# 20240717-7439.net
KiCad netlist of a schematic drawn in EAGLE
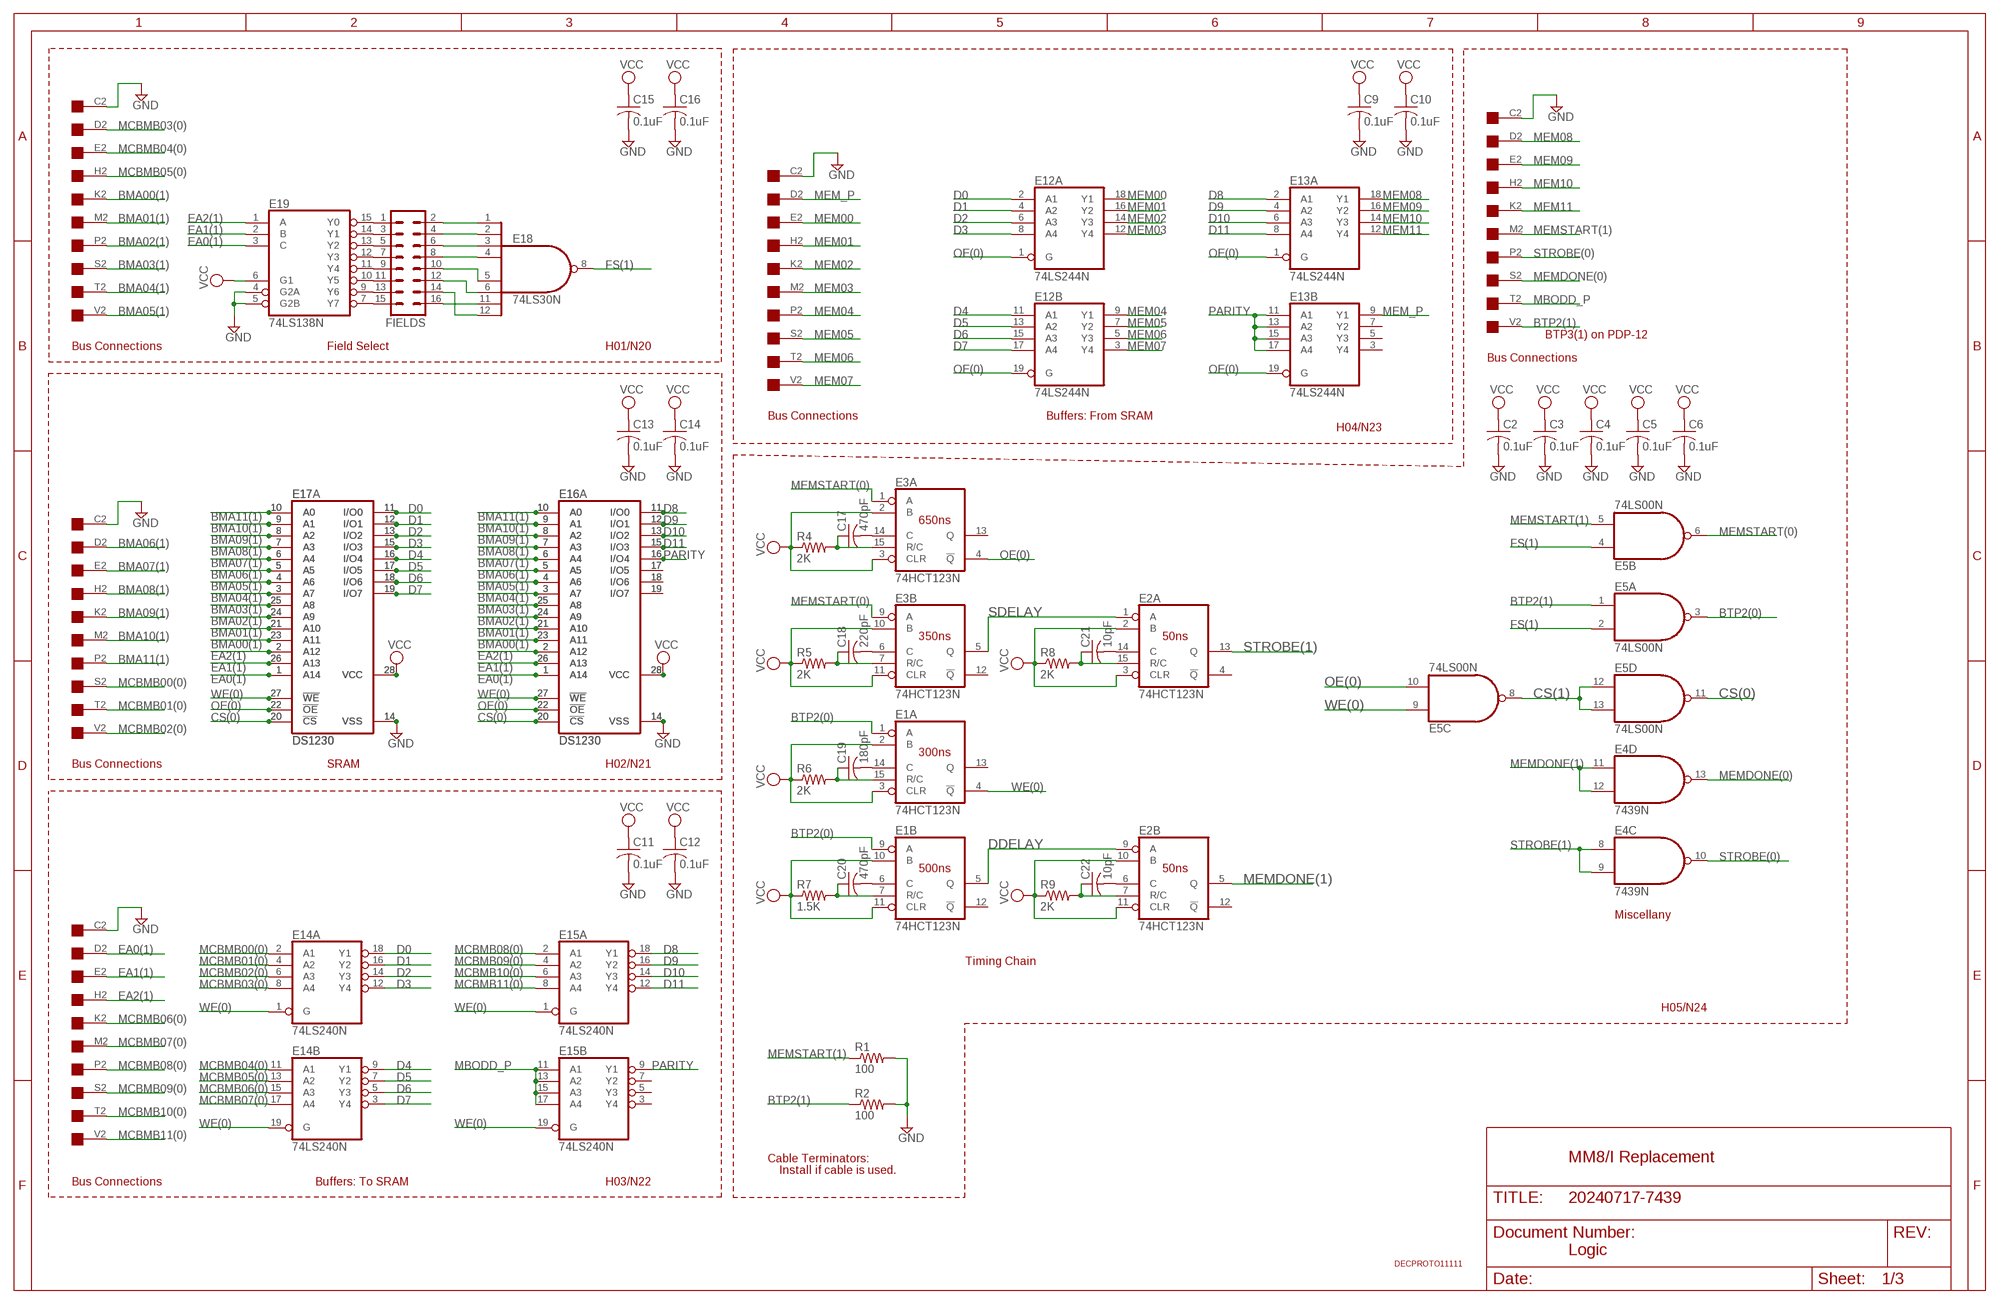
[diagram p0: schematic, sheet 1]
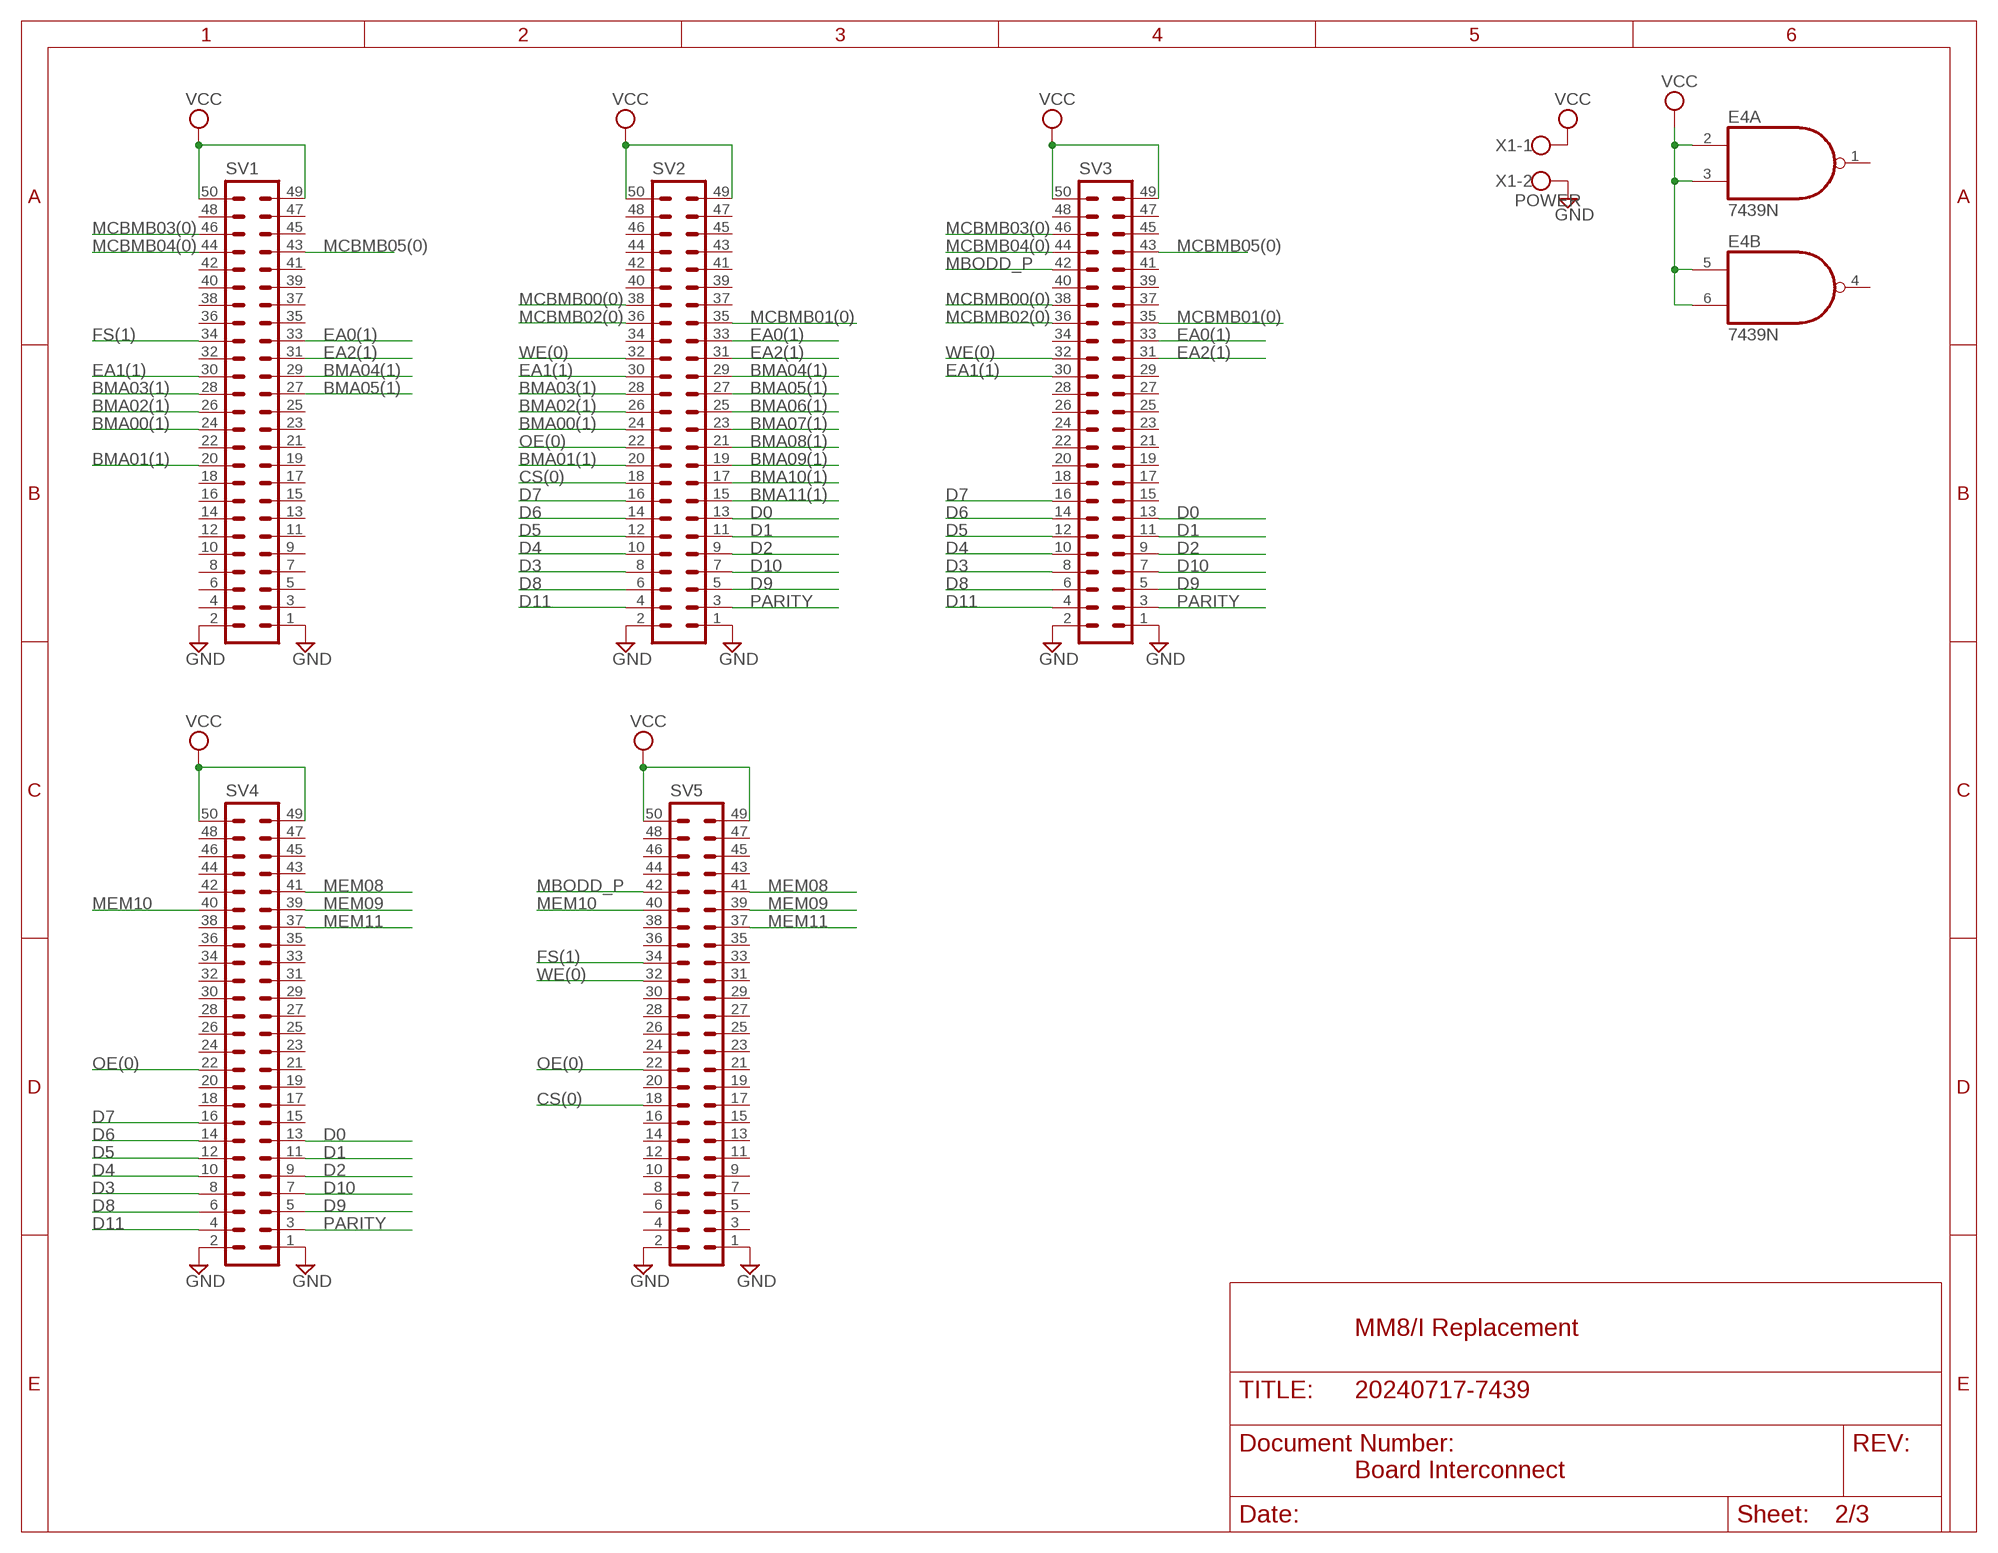
[diagram p1: schematic, sheet 2]
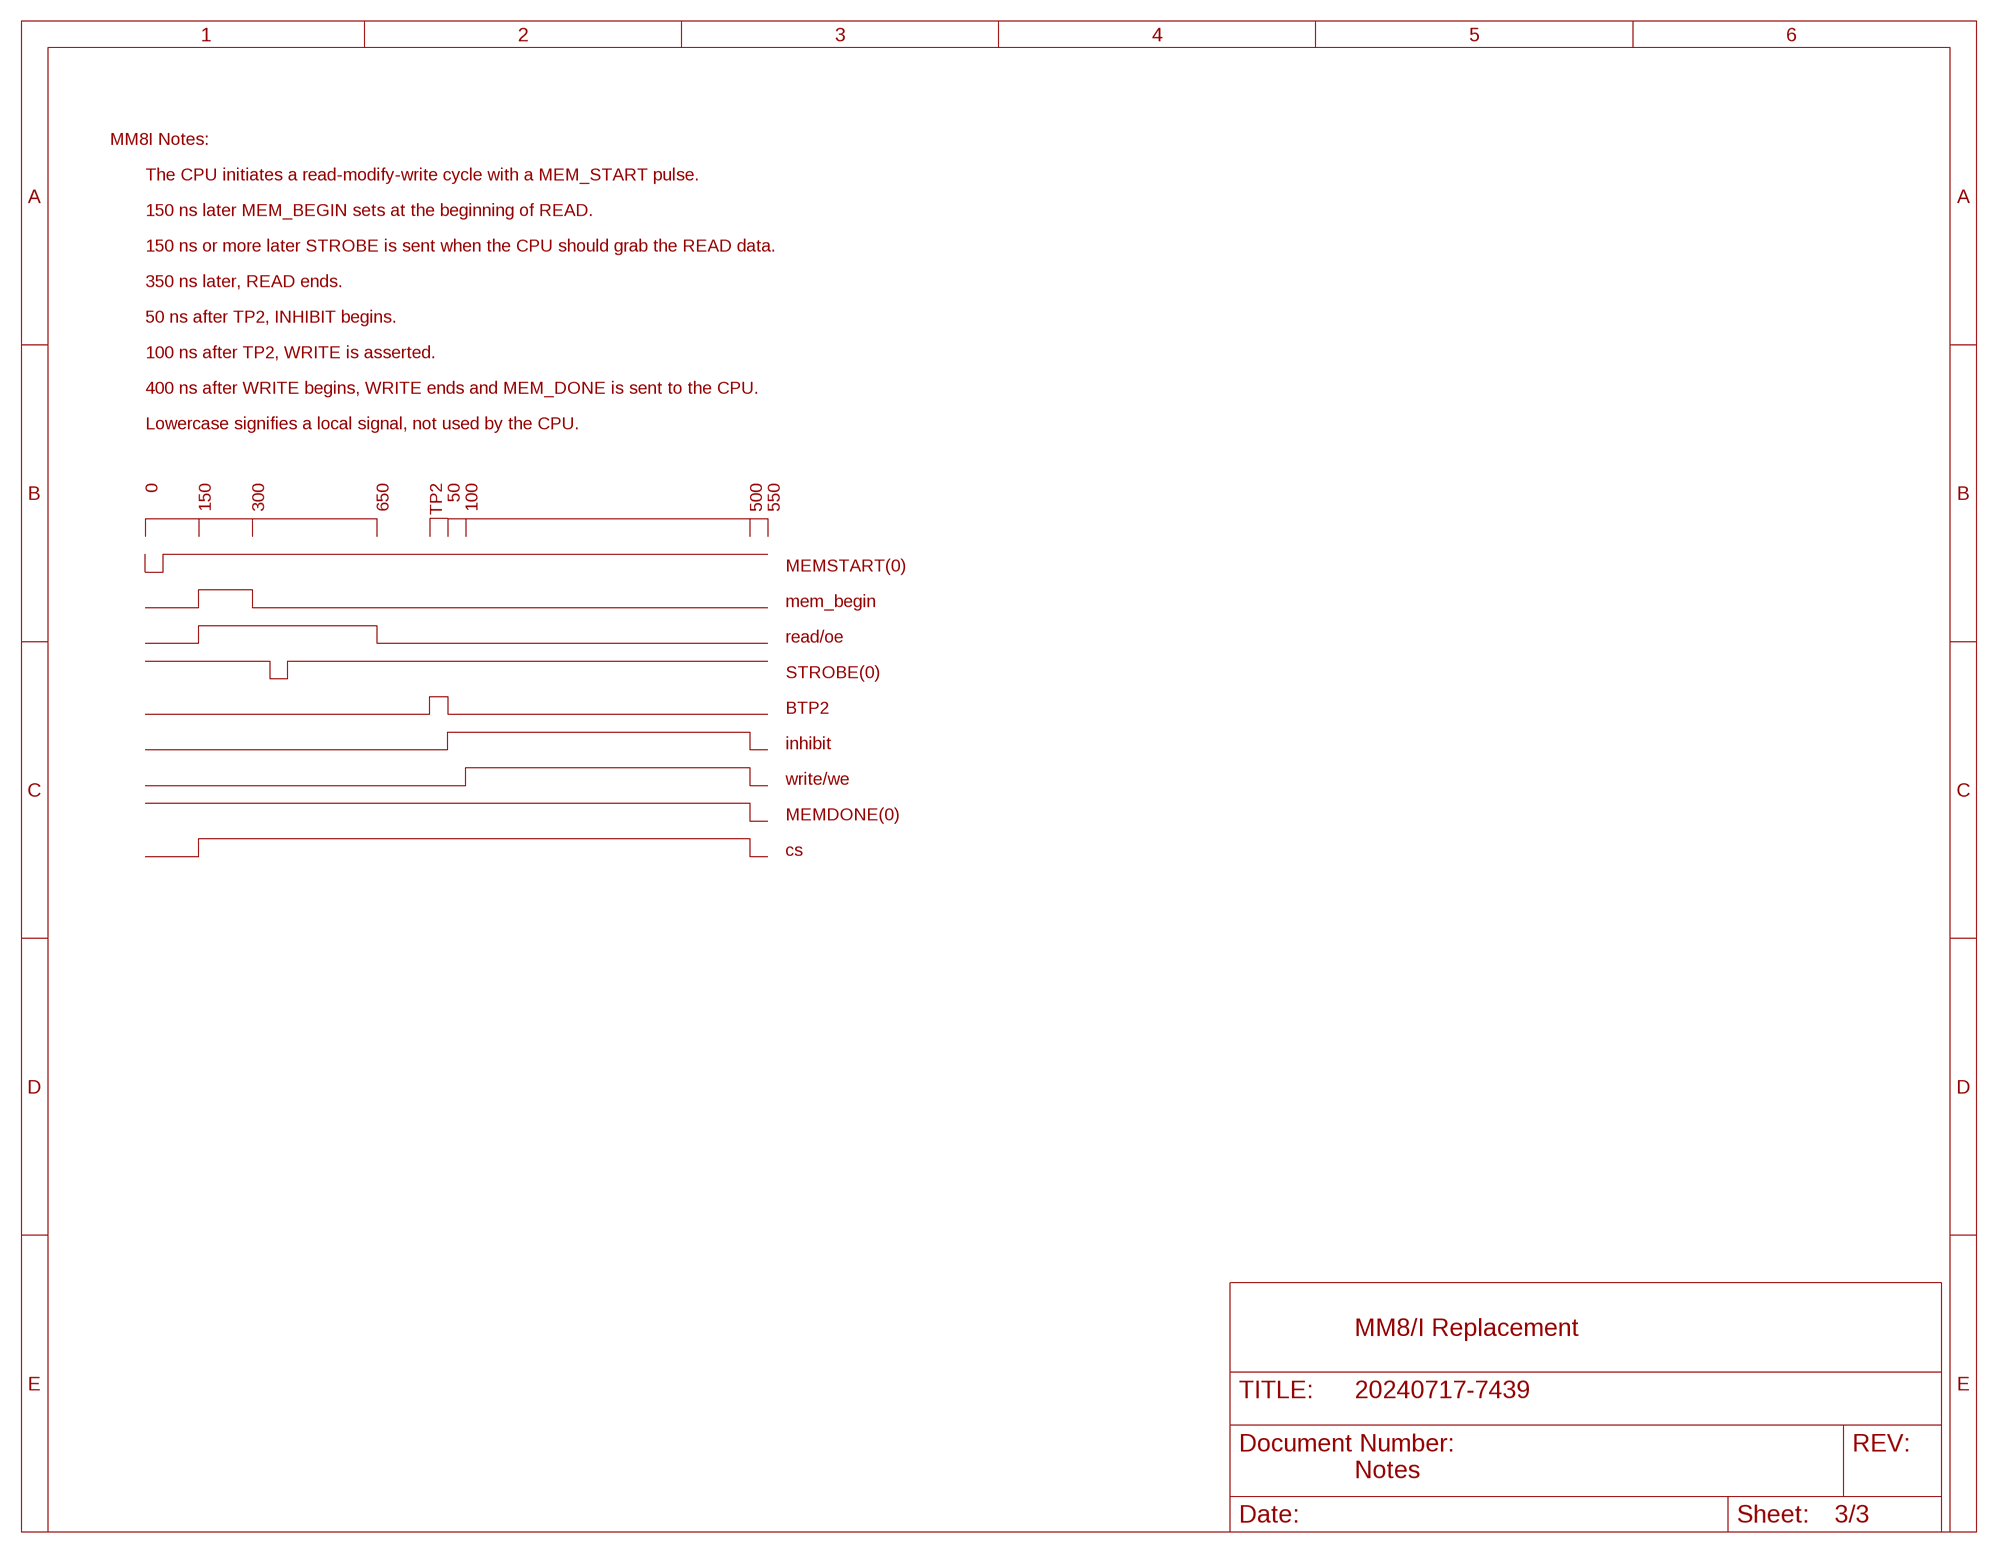
[diagram p2: schematic, sheet 3]

(export (version "E")
  (design (tool "Eeschema 10.0.6"))
  (components
    (comp (ref "C2")
      (value "0.1uF")
      (footprint "eagle-import:C050-025X075")
      (libsource (lib "eagle-import") (part "C-US050-025X075"))
    )
    (comp (ref "C3")
      (value "0.1uF")
      (footprint "eagle-import:C050-025X075")
      (libsource (lib "eagle-import") (part "C-US050-025X075"))
    )
    (comp (ref "C4")
      (value "0.1uF")
      (footprint "eagle-import:C050-025X075")
      (libsource (lib "eagle-import") (part "C-US050-025X075"))
    )
    (comp (ref "C5")
      (value "0.1uF")
      (footprint "eagle-import:C050-025X075")
      (libsource (lib "eagle-import") (part "C-US050-025X075"))
    )
    (comp (ref "C6")
      (value "0.1uF")
      (footprint "eagle-import:C050-025X075")
      (libsource (lib "eagle-import") (part "C-US050-025X075"))
    )
    (comp (ref "C9")
      (value "0.1uF")
      (footprint "eagle-import:C050-025X075")
      (libsource (lib "eagle-import") (part "C-US050-025X075"))
    )
    (comp (ref "C10")
      (value "0.1uF")
      (footprint "eagle-import:C050-025X075")
      (libsource (lib "eagle-import") (part "C-US050-025X075"))
    )
    (comp (ref "C11")
      (value "0.1uF")
      (footprint "eagle-import:C050-025X075")
      (libsource (lib "eagle-import") (part "C-US050-025X075"))
    )
    (comp (ref "C12")
      (value "0.1uF")
      (footprint "eagle-import:C050-025X075")
      (libsource (lib "eagle-import") (part "C-US050-025X075"))
    )
    (comp (ref "C13")
      (value "0.1uF")
      (footprint "eagle-import:C050-025X075")
      (libsource (lib "eagle-import") (part "C-US050-025X075"))
    )
    (comp (ref "C14")
      (value "0.1uF")
      (footprint "eagle-import:C050-025X075")
      (libsource (lib "eagle-import") (part "C-US050-025X075"))
    )
    (comp (ref "C15")
      (value "0.1uF")
      (footprint "eagle-import:C050-025X075")
      (libsource (lib "eagle-import") (part "C-US050-025X075"))
    )
    (comp (ref "C16")
      (value "0.1uF")
      (footprint "eagle-import:C050-025X075")
      (libsource (lib "eagle-import") (part "C-US050-025X075"))
    )
    (comp (ref "C17")
      (value "470pF")
      (footprint "eagle-import:C050-025X075")
      (libsource (lib "eagle-import") (part "C-US050-025X075"))
    )
    (comp (ref "C18")
      (value "220pF")
      (footprint "eagle-import:C050-025X075")
      (libsource (lib "eagle-import") (part "C-US050-025X075"))
    )
    (comp (ref "C19")
      (value "180pF")
      (footprint "eagle-import:C050-025X075")
      (libsource (lib "eagle-import") (part "C-US050-025X075"))
    )
    (comp (ref "C20")
      (value "470pF")
      (footprint "eagle-import:C050-025X075")
      (libsource (lib "eagle-import") (part "C-US050-025X075"))
    )
    (comp (ref "C21")
      (value "10pF")
      (footprint "eagle-import:C050-025X075")
      (libsource (lib "eagle-import") (part "C-US050-025X075"))
    )
    (comp (ref "C22")
      (value "10pF")
      (footprint "eagle-import:C050-025X075")
      (libsource (lib "eagle-import") (part "C-US050-025X075"))
    )
    (comp (ref "E1")
      (value "74HCT123N")
      (footprint "eagle-import:DIL16")
      (libsource (lib "eagle-import") (part "74123NLS"))
    )
    (comp (ref "E2")
      (value "74HCT123N")
      (footprint "eagle-import:DIL16")
      (libsource (lib "eagle-import") (part "74123NLS"))
    )
    (comp (ref "E3")
      (value "74HCT123N")
      (footprint "eagle-import:DIL16")
      (libsource (lib "eagle-import") (part "74123NLS"))
    )
    (comp (ref "E4")
      (value "7439N")
      (footprint "eagle-import:DIL14")
      (libsource (lib "eagle-import") (part "7401NLS"))
    )
    (comp (ref "E5")
      (value "74LS00N")
      (footprint "eagle-import:DIL14")
      (libsource (lib "eagle-import") (part "7400NLS"))
    )
    (comp (ref "E12")
      (value "74LS244N")
      (footprint "eagle-import:DIL20")
      (libsource (lib "eagle-import") (part "74244NS"))
    )
    (comp (ref "E13")
      (value "74LS244N")
      (footprint "eagle-import:DIL20")
      (libsource (lib "eagle-import") (part "74244NS"))
    )
    (comp (ref "E14")
      (value "74LS240N")
      (footprint "eagle-import:DIL20")
      (libsource (lib "eagle-import") (part "74240NS"))
    )
    (comp (ref "E15")
      (value "74LS240N")
      (footprint "eagle-import:DIL20")
      (libsource (lib "eagle-import") (part "74240NS"))
    )
    (comp (ref "E16")
      (value "DS1230")
      (footprint "eagle-import:DIL28-6")
      (libsource (lib "eagle-import") (part "62256P"))
    )
    (comp (ref "E16A")
      (value "DS1230")
      (footprint "eagle-import:DIL28-3")
      (libsource (lib "eagle-import") (part "62832P"))
    )
    (comp (ref "E17")
      (value "DS1230")
      (footprint "eagle-import:DIL28-6")
      (libsource (lib "eagle-import") (part "62256P"))
    )
    (comp (ref "E17A")
      (value "DS1230")
      (footprint "eagle-import:DIL28-3")
      (libsource (lib "eagle-import") (part "62832P"))
    )
    (comp (ref "E18")
      (value "74LS30N")
      (footprint "eagle-import:DIL14")
      (libsource (lib "eagle-import") (part "7430NLS"))
    )
    (comp (ref "E19")
      (value "74LS138N")
      (footprint "eagle-import:DIL16")
      (libsource (lib "eagle-import") (part "74138NLS"))
    )
    (comp (ref "FIELDS")
      (value "MA08-2")
      (footprint "eagle-import:MA08-2")
      (libsource (lib "eagle-import") (part "MA08-2"))
    )
    (comp (ref "H01")
      (value "EDGE-1")
      (footprint "eagle-import:EDGE-CON1")
      (libsource (lib "eagle-import") (part "EDGE-1"))
    )
    (comp (ref "H02")
      (value "EDGE-1")
      (footprint "eagle-import:EDGE-CON1")
      (libsource (lib "eagle-import") (part "EDGE-1"))
    )
    (comp (ref "H03")
      (value "EDGE-1")
      (footprint "eagle-import:EDGE-CON1")
      (libsource (lib "eagle-import") (part "EDGE-1"))
    )
    (comp (ref "H04")
      (value "EDGE-1")
      (footprint "eagle-import:EDGE-CON1")
      (libsource (lib "eagle-import") (part "EDGE-1"))
    )
    (comp (ref "H05")
      (value "EDGE-1")
      (footprint "eagle-import:EDGE-CON1")
      (libsource (lib "eagle-import") (part "EDGE-1"))
    )
    (comp (ref "R1")
      (value "100")
      (footprint "eagle-import:0207_10")
      (libsource (lib "eagle-import") (part "R-US_0207/10"))
    )
    (comp (ref "R2")
      (value "100")
      (footprint "eagle-import:0207_10")
      (libsource (lib "eagle-import") (part "R-US_0207/10"))
    )
    (comp (ref "R4")
      (value "2K")
      (footprint "eagle-import:0207_10")
      (libsource (lib "eagle-import") (part "R-US_0207/10"))
    )
    (comp (ref "R5")
      (value "2K")
      (footprint "eagle-import:0207_10")
      (libsource (lib "eagle-import") (part "R-US_0207/10"))
    )
    (comp (ref "R6")
      (value "2K")
      (footprint "eagle-import:0207_10")
      (libsource (lib "eagle-import") (part "R-US_0207/10"))
    )
    (comp (ref "R7")
      (value "1.5K")
      (footprint "eagle-import:0207_10")
      (libsource (lib "eagle-import") (part "R-US_0207/10"))
    )
    (comp (ref "R8")
      (value "2K")
      (footprint "eagle-import:0207_10")
      (libsource (lib "eagle-import") (part "R-US_0207/10"))
    )
    (comp (ref "R9")
      (value "2K")
      (footprint "eagle-import:0207_10")
      (libsource (lib "eagle-import") (part "R-US_0207/10"))
    )
    (comp (ref "U$6")
      (value "DECPROTO11111")
      (footprint "eagle-import:DECPROTO11111")
      (libsource (lib "eagle-import") (part "DECPROTO11111"))
    )
    (comp (ref "SV1")
      (value "ML50L")
      (footprint "eagle-import:ML50L")
      (libsource (lib "eagle-import") (part "ML50L"))
    )
    (comp (ref "SV2")
      (value "ML50L")
      (footprint "eagle-import:ML50L")
      (libsource (lib "eagle-import") (part "ML50L"))
    )
    (comp (ref "SV3")
      (value "ML50L")
      (footprint "eagle-import:ML50L")
      (libsource (lib "eagle-import") (part "ML50L"))
    )
    (comp (ref "SV4")
      (value "ML50L")
      (footprint "eagle-import:ML50L")
      (libsource (lib "eagle-import") (part "ML50L"))
    )
    (comp (ref "SV5")
      (value "ML50L")
      (footprint "eagle-import:ML50L")
      (libsource (lib "eagle-import") (part "ML50L"))
    )
    (comp (ref "X1")
      (value "POWER")
      (footprint "eagle-import:W237-102")
      (fields (field (name "MPN") "237-102"))
      (libsource (lib "eagle-import") (part "W237-102"))
    )
  )
  (nets
    (net (code "1") (name "BMA00(1)") (class "Default")
      (node (ref "E16") (pin "23") (pinfunction "A11_23") (pintype "input"))
      (node (ref "E16A") (pin "23") (pinfunction "A11_23") (pintype "input"))
      (node (ref "E17") (pin "23") (pinfunction "A11_23") (pintype "input"))
      (node (ref "E17A") (pin "23") (pinfunction "A11_23") (pintype "input"))
      (node (ref "H01") (pin "K2") (pinfunction "1_K2") (pintype "bidirectional"))
      (node (ref "SV1") (pin "24") (pinfunction "24_24") (pintype "passive"))
      (node (ref "SV2") (pin "24") (pinfunction "24_24") (pintype "passive"))
    )
    (net (code "2") (name "BMA01(1)") (class "Default")
      (node (ref "E16") (pin "21") (pinfunction "A10_21") (pintype "input"))
      (node (ref "E16A") (pin "21") (pinfunction "A10_21") (pintype "input"))
      (node (ref "E17") (pin "21") (pinfunction "A10_21") (pintype "input"))
      (node (ref "E17A") (pin "21") (pinfunction "A10_21") (pintype "input"))
      (node (ref "H01") (pin "M2") (pinfunction "1_M2") (pintype "bidirectional"))
      (node (ref "SV1") (pin "20") (pinfunction "20_20") (pintype "passive"))
      (node (ref "SV2") (pin "20") (pinfunction "20_20") (pintype "passive"))
    )
    (net (code "3") (name "BMA02(1)") (class "Default")
      (node (ref "E16") (pin "24") (pinfunction "A9_24") (pintype "input"))
      (node (ref "E16A") (pin "24") (pinfunction "A9_24") (pintype "input"))
      (node (ref "E17") (pin "24") (pinfunction "A9_24") (pintype "input"))
      (node (ref "E17A") (pin "24") (pinfunction "A9_24") (pintype "input"))
      (node (ref "H01") (pin "P2") (pinfunction "1_P2") (pintype "bidirectional"))
      (node (ref "SV1") (pin "26") (pinfunction "26_26") (pintype "passive"))
      (node (ref "SV2") (pin "26") (pinfunction "26_26") (pintype "passive"))
    )
    (net (code "4") (name "BMA03(1)") (class "Default")
      (node (ref "E16") (pin "25") (pinfunction "A8_25") (pintype "input"))
      (node (ref "E16A") (pin "25") (pinfunction "A8_25") (pintype "input"))
      (node (ref "E17") (pin "25") (pinfunction "A8_25") (pintype "input"))
      (node (ref "E17A") (pin "25") (pinfunction "A8_25") (pintype "input"))
      (node (ref "H01") (pin "S2") (pinfunction "1_S2") (pintype "bidirectional"))
      (node (ref "SV1") (pin "28") (pinfunction "28_28") (pintype "passive"))
      (node (ref "SV2") (pin "28") (pinfunction "28_28") (pintype "passive"))
    )
    (net (code "5") (name "BMA04(1)") (class "Default")
      (node (ref "E16") (pin "3") (pinfunction "A7_3") (pintype "input"))
      (node (ref "E16A") (pin "3") (pinfunction "A7_3") (pintype "input"))
      (node (ref "E17") (pin "3") (pinfunction "A7_3") (pintype "input"))
      (node (ref "E17A") (pin "3") (pinfunction "A7_3") (pintype "input"))
      (node (ref "H01") (pin "T2") (pinfunction "1_T2") (pintype "bidirectional"))
      (node (ref "SV1") (pin "29") (pinfunction "29_29") (pintype "passive"))
      (node (ref "SV2") (pin "29") (pinfunction "29_29") (pintype "passive"))
    )
    (net (code "6") (name "BMA05(1)") (class "Default")
      (node (ref "E16") (pin "4") (pinfunction "A6_4") (pintype "input"))
      (node (ref "E16A") (pin "4") (pinfunction "A6_4") (pintype "input"))
      (node (ref "E17") (pin "4") (pinfunction "A6_4") (pintype "input"))
      (node (ref "E17A") (pin "4") (pinfunction "A6_4") (pintype "input"))
      (node (ref "H01") (pin "V2") (pinfunction "1_V2") (pintype "bidirectional"))
      (node (ref "SV1") (pin "27") (pinfunction "27_27") (pintype "passive"))
      (node (ref "SV2") (pin "27") (pinfunction "27_27") (pintype "passive"))
    )
    (net (code "7") (name "BMA06(1)") (class "Default")
      (node (ref "E16") (pin "5") (pinfunction "A5_5") (pintype "input"))
      (node (ref "E16A") (pin "5") (pinfunction "A5_5") (pintype "input"))
      (node (ref "E17") (pin "5") (pinfunction "A5_5") (pintype "input"))
      (node (ref "E17A") (pin "5") (pinfunction "A5_5") (pintype "input"))
      (node (ref "H02") (pin "D2") (pinfunction "1_D2") (pintype "bidirectional"))
      (node (ref "SV2") (pin "25") (pinfunction "25_25") (pintype "passive"))
    )
    (net (code "8") (name "BMA07(1)") (class "Default")
      (node (ref "E16") (pin "6") (pinfunction "A4_6") (pintype "input"))
      (node (ref "E16A") (pin "6") (pinfunction "A4_6") (pintype "input"))
      (node (ref "E17") (pin "6") (pinfunction "A4_6") (pintype "input"))
      (node (ref "E17A") (pin "6") (pinfunction "A4_6") (pintype "input"))
      (node (ref "H02") (pin "E2") (pinfunction "1_E2") (pintype "bidirectional"))
      (node (ref "SV2") (pin "23") (pinfunction "23_23") (pintype "passive"))
    )
    (net (code "9") (name "BMA08(1)") (class "Default")
      (node (ref "E16") (pin "7") (pinfunction "A3_7") (pintype "input"))
      (node (ref "E16A") (pin "7") (pinfunction "A3_7") (pintype "input"))
      (node (ref "E17") (pin "7") (pinfunction "A3_7") (pintype "input"))
      (node (ref "E17A") (pin "7") (pinfunction "A3_7") (pintype "input"))
      (node (ref "H02") (pin "H2") (pinfunction "1_H2") (pintype "bidirectional"))
      (node (ref "SV2") (pin "21") (pinfunction "21_21") (pintype "passive"))
    )
    (net (code "10") (name "BMA09(1)") (class "Default")
      (node (ref "E16") (pin "8") (pinfunction "A2_8") (pintype "input"))
      (node (ref "E16A") (pin "8") (pinfunction "A2_8") (pintype "input"))
      (node (ref "E17") (pin "8") (pinfunction "A2_8") (pintype "input"))
      (node (ref "E17A") (pin "8") (pinfunction "A2_8") (pintype "input"))
      (node (ref "H02") (pin "K2") (pinfunction "1_K2") (pintype "bidirectional"))
      (node (ref "SV2") (pin "19") (pinfunction "19_19") (pintype "passive"))
    )
    (net (code "11") (name "BMA10(1)") (class "Default")
      (node (ref "E16") (pin "9") (pinfunction "A1_9") (pintype "input"))
      (node (ref "E16A") (pin "9") (pinfunction "A1_9") (pintype "input"))
      (node (ref "E17") (pin "9") (pinfunction "A1_9") (pintype "input"))
      (node (ref "E17A") (pin "9") (pinfunction "A1_9") (pintype "input"))
      (node (ref "H02") (pin "M2") (pinfunction "1_M2") (pintype "bidirectional"))
      (node (ref "SV2") (pin "17") (pinfunction "17_17") (pintype "passive"))
    )
    (net (code "12") (name "BMA11(1)") (class "Default")
      (node (ref "E16") (pin "10") (pinfunction "A0_10") (pintype "input"))
      (node (ref "E16A") (pin "10") (pinfunction "A0_10") (pintype "input"))
      (node (ref "E17") (pin "10") (pinfunction "A0_10") (pintype "input"))
      (node (ref "E17A") (pin "10") (pinfunction "A0_10") (pintype "input"))
      (node (ref "H02") (pin "P2") (pinfunction "1_P2") (pintype "bidirectional"))
      (node (ref "SV2") (pin "15") (pinfunction "15_15") (pintype "passive"))
    )
    (net (code "13") (name "BTP2(0)") (class "Default")
      (node (ref "E1") (pin "1") (pinfunction "A_1") (pintype "input"))
      (node (ref "E1") (pin "9") (pinfunction "A_9") (pintype "input"))
      (node (ref "E5") (pin "3") (pinfunction "O_3") (pintype "output"))
    )
    (net (code "14") (name "BTP2(1)") (class "Default")
      (node (ref "E5") (pin "1") (pinfunction "I0_1") (pintype "input"))
      (node (ref "H05") (pin "V2") (pinfunction "1_V2") (pintype "bidirectional"))
      (node (ref "R2") (pin "1") (pinfunction "1_1") (pintype "passive"))
    )
    (net (code "15") (name "CS(0)") (class "Default")
      (node (ref "E16") (pin "20") (pinfunction "~{CS}_20") (pintype "input"))
      (node (ref "E16A") (pin "20") (pinfunction "~{CS}_20") (pintype "input"))
      (node (ref "E17") (pin "20") (pinfunction "~{CS}_20") (pintype "input"))
      (node (ref "E17A") (pin "20") (pinfunction "~{CS}_20") (pintype "input"))
      (node (ref "E5") (pin "11") (pinfunction "O_11") (pintype "output"))
      (node (ref "SV2") (pin "18") (pinfunction "18_18") (pintype "passive"))
      (node (ref "SV5") (pin "18") (pinfunction "18_18") (pintype "passive"))
    )
    (net (code "16") (name "CS(1)") (class "Default")
      (node (ref "E5") (pin "12") (pinfunction "I0_12") (pintype "input"))
      (node (ref "E5") (pin "13") (pinfunction "I1_13") (pintype "input"))
      (node (ref "E5") (pin "8") (pinfunction "O_8") (pintype "output"))
    )
    (net (code "17") (name "D0") (class "Default")
      (node (ref "E12") (pin "2") (pinfunction "A1_2") (pintype "input"))
      (node (ref "E14") (pin "18") (pinfunction "Y1_18") (pintype "tri_state"))
      (node (ref "E17") (pin "11") (pinfunction "I/O0_11") (pintype "bidirectional"))
      (node (ref "E17A") (pin "11") (pinfunction "I/O0_11") (pintype "bidirectional"))
      (node (ref "SV2") (pin "13") (pinfunction "13_13") (pintype "passive"))
      (node (ref "SV3") (pin "13") (pinfunction "13_13") (pintype "passive"))
      (node (ref "SV4") (pin "13") (pinfunction "13_13") (pintype "passive"))
    )
    (net (code "18") (name "D1") (class "Default")
      (node (ref "E12") (pin "4") (pinfunction "A2_4") (pintype "input"))
      (node (ref "E14") (pin "16") (pinfunction "Y2_16") (pintype "tri_state"))
      (node (ref "E17") (pin "12") (pinfunction "I/O1_12") (pintype "bidirectional"))
      (node (ref "E17A") (pin "12") (pinfunction "I/O1_12") (pintype "bidirectional"))
      (node (ref "SV2") (pin "11") (pinfunction "11_11") (pintype "passive"))
      (node (ref "SV3") (pin "11") (pinfunction "11_11") (pintype "passive"))
      (node (ref "SV4") (pin "11") (pinfunction "11_11") (pintype "passive"))
    )
    (net (code "19") (name "D2") (class "Default")
      (node (ref "E12") (pin "6") (pinfunction "A3_6") (pintype "input"))
      (node (ref "E14") (pin "14") (pinfunction "Y3_14") (pintype "tri_state"))
      (node (ref "E17") (pin "13") (pinfunction "I/O2_13") (pintype "bidirectional"))
      (node (ref "E17A") (pin "13") (pinfunction "I/O2_13") (pintype "bidirectional"))
      (node (ref "SV2") (pin "9") (pinfunction "9_9") (pintype "passive"))
      (node (ref "SV3") (pin "9") (pinfunction "9_9") (pintype "passive"))
      (node (ref "SV4") (pin "9") (pinfunction "9_9") (pintype "passive"))
    )
    (net (code "20") (name "D3") (class "Default")
      (node (ref "E12") (pin "8") (pinfunction "A4_8") (pintype "input"))
      (node (ref "E14") (pin "12") (pinfunction "Y4_12") (pintype "tri_state"))
      (node (ref "E17") (pin "15") (pinfunction "I/O3_15") (pintype "bidirectional"))
      (node (ref "E17A") (pin "15") (pinfunction "I/O3_15") (pintype "bidirectional"))
      (node (ref "SV2") (pin "8") (pinfunction "8_8") (pintype "passive"))
      (node (ref "SV3") (pin "8") (pinfunction "8_8") (pintype "passive"))
      (node (ref "SV4") (pin "8") (pinfunction "8_8") (pintype "passive"))
    )
    (net (code "21") (name "D4") (class "Default")
      (node (ref "E12") (pin "11") (pinfunction "A1_11") (pintype "input"))
      (node (ref "E14") (pin "9") (pinfunction "Y1_9") (pintype "tri_state"))
      (node (ref "E17") (pin "16") (pinfunction "I/O4_16") (pintype "bidirectional"))
      (node (ref "E17A") (pin "16") (pinfunction "I/O4_16") (pintype "bidirectional"))
      (node (ref "SV2") (pin "10") (pinfunction "10_10") (pintype "passive"))
      (node (ref "SV3") (pin "10") (pinfunction "10_10") (pintype "passive"))
      (node (ref "SV4") (pin "10") (pinfunction "10_10") (pintype "passive"))
    )
    (net (code "22") (name "D5") (class "Default")
      (node (ref "E12") (pin "13") (pinfunction "A2_13") (pintype "input"))
      (node (ref "E14") (pin "7") (pinfunction "Y2_7") (pintype "tri_state"))
      (node (ref "E17") (pin "17") (pinfunction "I/O5_17") (pintype "bidirectional"))
      (node (ref "E17A") (pin "17") (pinfunction "I/O5_17") (pintype "bidirectional"))
      (node (ref "SV2") (pin "12") (pinfunction "12_12") (pintype "passive"))
      (node (ref "SV3") (pin "12") (pinfunction "12_12") (pintype "passive"))
      (node (ref "SV4") (pin "12") (pinfunction "12_12") (pintype "passive"))
    )
    (net (code "23") (name "D6") (class "Default")
      (node (ref "E12") (pin "15") (pinfunction "A3_15") (pintype "input"))
      (node (ref "E14") (pin "5") (pinfunction "Y3_5") (pintype "tri_state"))
      (node (ref "E17") (pin "18") (pinfunction "I/O6_18") (pintype "bidirectional"))
      (node (ref "E17A") (pin "18") (pinfunction "I/O6_18") (pintype "bidirectional"))
      (node (ref "SV2") (pin "14") (pinfunction "14_14") (pintype "passive"))
      (node (ref "SV3") (pin "14") (pinfunction "14_14") (pintype "passive"))
      (node (ref "SV4") (pin "14") (pinfunction "14_14") (pintype "passive"))
    )
    (net (code "24") (name "D7") (class "Default")
      (node (ref "E12") (pin "17") (pinfunction "A4_17") (pintype "input"))
      (node (ref "E14") (pin "3") (pinfunction "Y4_3") (pintype "tri_state"))
      (node (ref "E17") (pin "19") (pinfunction "I/O7_19") (pintype "bidirectional"))
      (node (ref "E17A") (pin "19") (pinfunction "I/O7_19") (pintype "bidirectional"))
      (node (ref "SV2") (pin "16") (pinfunction "16_16") (pintype "passive"))
      (node (ref "SV3") (pin "16") (pinfunction "16_16") (pintype "passive"))
      (node (ref "SV4") (pin "16") (pinfunction "16_16") (pintype "passive"))
    )
    (net (code "25") (name "D8") (class "Default")
      (node (ref "E13") (pin "2") (pinfunction "A1_2") (pintype "input"))
      (node (ref "E15") (pin "18") (pinfunction "Y1_18") (pintype "tri_state"))
      (node (ref "E16") (pin "11") (pinfunction "I/O0_11") (pintype "bidirectional"))
      (node (ref "E16A") (pin "11") (pinfunction "I/O0_11") (pintype "bidirectional"))
      (node (ref "SV2") (pin "6") (pinfunction "6_6") (pintype "passive"))
      (node (ref "SV3") (pin "6") (pinfunction "6_6") (pintype "passive"))
      (node (ref "SV4") (pin "6") (pinfunction "6_6") (pintype "passive"))
    )
    (net (code "26") (name "D9") (class "Default")
      (node (ref "E13") (pin "4") (pinfunction "A2_4") (pintype "input"))
      (node (ref "E15") (pin "16") (pinfunction "Y2_16") (pintype "tri_state"))
      (node (ref "E16") (pin "12") (pinfunction "I/O1_12") (pintype "bidirectional"))
      (node (ref "E16A") (pin "12") (pinfunction "I/O1_12") (pintype "bidirectional"))
      (node (ref "SV2") (pin "5") (pinfunction "5_5") (pintype "passive"))
      (node (ref "SV3") (pin "5") (pinfunction "5_5") (pintype "passive"))
      (node (ref "SV4") (pin "5") (pinfunction "5_5") (pintype "passive"))
    )
    (net (code "27") (name "D10") (class "Default")
      (node (ref "E13") (pin "6") (pinfunction "A3_6") (pintype "input"))
      (node (ref "E15") (pin "14") (pinfunction "Y3_14") (pintype "tri_state"))
      (node (ref "E16") (pin "13") (pinfunction "I/O2_13") (pintype "bidirectional"))
      (node (ref "E16A") (pin "13") (pinfunction "I/O2_13") (pintype "bidirectional"))
      (node (ref "SV2") (pin "7") (pinfunction "7_7") (pintype "passive"))
      (node (ref "SV3") (pin "7") (pinfunction "7_7") (pintype "passive"))
      (node (ref "SV4") (pin "7") (pinfunction "7_7") (pintype "passive"))
    )
    (net (code "28") (name "D11") (class "Default")
      (node (ref "E13") (pin "8") (pinfunction "A4_8") (pintype "input"))
      (node (ref "E15") (pin "12") (pinfunction "Y4_12") (pintype "tri_state"))
      (node (ref "E16") (pin "15") (pinfunction "I/O3_15") (pintype "bidirectional"))
      (node (ref "E16A") (pin "15") (pinfunction "I/O3_15") (pintype "bidirectional"))
      (node (ref "SV2") (pin "4") (pinfunction "4_4") (pintype "passive"))
      (node (ref "SV3") (pin "4") (pinfunction "4_4") (pintype "passive"))
      (node (ref "SV4") (pin "4") (pinfunction "4_4") (pintype "passive"))
    )
    (net (code "29") (name "DDELAY") (class "Default")
      (node (ref "E1") (pin "5") (pinfunction "Q_5") (pintype "output"))
      (node (ref "E2") (pin "9") (pinfunction "A_9") (pintype "input"))
    )
    (net (code "30") (name "EA0(1)") (class "Default")
      (node (ref "E16") (pin "1") (pinfunction "A14_1") (pintype "input"))
      (node (ref "E16A") (pin "1") (pinfunction "A14_1") (pintype "input"))
      (node (ref "E17") (pin "1") (pinfunction "A14_1") (pintype "input"))
      (node (ref "E17A") (pin "1") (pinfunction "A14_1") (pintype "input"))
      (node (ref "E19") (pin "3") (pinfunction "C_3") (pintype "input"))
      (node (ref "H03") (pin "D2") (pinfunction "1_D2") (pintype "bidirectional"))
      (node (ref "SV1") (pin "33") (pinfunction "33_33") (pintype "passive"))
      (node (ref "SV2") (pin "33") (pinfunction "33_33") (pintype "passive"))
      (node (ref "SV3") (pin "33") (pinfunction "33_33") (pintype "passive"))
    )
    (net (code "31") (name "EA1(1)") (class "Default")
      (node (ref "E16") (pin "26") (pinfunction "A13_26") (pintype "input"))
      (node (ref "E16A") (pin "26") (pinfunction "A13_26") (pintype "input"))
      (node (ref "E17") (pin "26") (pinfunction "A13_26") (pintype "input"))
      (node (ref "E17A") (pin "26") (pinfunction "A13_26") (pintype "input"))
      (node (ref "E19") (pin "2") (pinfunction "B_2") (pintype "input"))
      (node (ref "H03") (pin "E2") (pinfunction "1_E2") (pintype "bidirectional"))
      (node (ref "SV1") (pin "30") (pinfunction "30_30") (pintype "passive"))
      (node (ref "SV2") (pin "30") (pinfunction "30_30") (pintype "passive"))
      (node (ref "SV3") (pin "30") (pinfunction "30_30") (pintype "passive"))
    )
    (net (code "32") (name "EA2(1)") (class "Default")
      (node (ref "E16") (pin "2") (pinfunction "A12_2") (pintype "input"))
      (node (ref "E16A") (pin "2") (pinfunction "A12_2") (pintype "input"))
      (node (ref "E17") (pin "2") (pinfunction "A12_2") (pintype "input"))
      (node (ref "E17A") (pin "2") (pinfunction "A12_2") (pintype "input"))
      (node (ref "E19") (pin "1") (pinfunction "A_1") (pintype "input"))
      (node (ref "H03") (pin "H2") (pinfunction "1_H2") (pintype "bidirectional"))
      (node (ref "SV1") (pin "31") (pinfunction "31_31") (pintype "passive"))
      (node (ref "SV2") (pin "31") (pinfunction "31_31") (pintype "passive"))
      (node (ref "SV3") (pin "31") (pinfunction "31_31") (pintype "passive"))
    )
    (net (code "33") (name "FS(1)") (class "Default")
      (node (ref "E18") (pin "8") (pinfunction "O_8") (pintype "output"))
      (node (ref "E5") (pin "2") (pinfunction "I1_2") (pintype "input"))
      (node (ref "E5") (pin "4") (pinfunction "I0_4") (pintype "input"))
      (node (ref "SV1") (pin "34") (pinfunction "34_34") (pintype "passive"))
      (node (ref "SV5") (pin "34") (pinfunction "34_34") (pintype "passive"))
    )
    (net (code "34") (name "GND") (class "Default")
      (node (ref "C10") (pin "2") (pinfunction "2_2") (pintype "passive"))
      (node (ref "C11") (pin "2") (pinfunction "2_2") (pintype "passive"))
      (node (ref "C12") (pin "2") (pinfunction "2_2") (pintype "passive"))
      (node (ref "C13") (pin "2") (pinfunction "2_2") (pintype "passive"))
      (node (ref "C14") (pin "2") (pinfunction "2_2") (pintype "passive"))
      (node (ref "C15") (pin "2") (pinfunction "2_2") (pintype "passive"))
      (node (ref "C16") (pin "2") (pinfunction "2_2") (pintype "passive"))
      (node (ref "C2") (pin "2") (pinfunction "2_2") (pintype "passive"))
      (node (ref "C3") (pin "2") (pinfunction "2_2") (pintype "passive"))
      (node (ref "C4") (pin "2") (pinfunction "2_2") (pintype "passive"))
      (node (ref "C5") (pin "2") (pinfunction "2_2") (pintype "passive"))
      (node (ref "C6") (pin "2") (pinfunction "2_2") (pintype "passive"))
      (node (ref "C9") (pin "2") (pinfunction "2_2") (pintype "passive"))
      (node (ref "E16") (pin "14") (pinfunction "VSS_14") (pintype "power_in"))
      (node (ref "E16A") (pin "14") (pinfunction "VSS_14") (pintype "power_in"))
      (node (ref "E17") (pin "14") (pinfunction "VSS_14") (pintype "power_in"))
      (node (ref "E17A") (pin "14") (pinfunction "VSS_14") (pintype "power_in"))
      (node (ref "E19") (pin "4") (pinfunction "G2A_4") (pintype "input"))
      (node (ref "E19") (pin "5") (pinfunction "G2B_5") (pintype "input"))
      (node (ref "H01") (pin "C2") (pinfunction "1_C2") (pintype "bidirectional"))
      (node (ref "H02") (pin "C2") (pinfunction "1_C2") (pintype "bidirectional"))
      (node (ref "H03") (pin "C2") (pinfunction "1_C2") (pintype "bidirectional"))
      (node (ref "H04") (pin "C2") (pinfunction "1_C2") (pintype "bidirectional"))
      (node (ref "H05") (pin "C2") (pinfunction "1_C2") (pintype "bidirectional"))
      (node (ref "R1") (pin "2") (pinfunction "2_2") (pintype "passive"))
      (node (ref "R2") (pin "2") (pinfunction "2_2") (pintype "passive"))
      (node (ref "SV1") (pin "1") (pinfunction "1_1") (pintype "passive"))
      (node (ref "SV1") (pin "2") (pinfunction "2_2") (pintype "passive"))
      (node (ref "SV2") (pin "1") (pinfunction "1_1") (pintype "passive"))
      (node (ref "SV2") (pin "2") (pinfunction "2_2") (pintype "passive"))
      (node (ref "SV3") (pin "1") (pinfunction "1_1") (pintype "passive"))
      (node (ref "SV3") (pin "2") (pinfunction "2_2") (pintype "passive"))
      (node (ref "SV4") (pin "1") (pinfunction "1_1") (pintype "passive"))
      (node (ref "SV4") (pin "2") (pinfunction "2_2") (pintype "passive"))
      (node (ref "SV5") (pin "1") (pinfunction "1_1") (pintype "passive"))
      (node (ref "SV5") (pin "2") (pinfunction "2_2") (pintype "passive"))
      (node (ref "X1") (pin "2") (pinfunction "KL_2") (pintype "passive"))
    )
    (net (code "35") (name "MBODD_P") (class "Default")
      (node (ref "E15") (pin "11") (pinfunction "A1_11") (pintype "input"))
      (node (ref "E15") (pin "13") (pinfunction "A2_13") (pintype "input"))
      (node (ref "E15") (pin "15") (pinfunction "A3_15") (pintype "input"))
      (node (ref "E15") (pin "17") (pinfunction "A4_17") (pintype "input"))
      (node (ref "H05") (pin "T2") (pinfunction "1_T2") (pintype "bidirectional"))
      (node (ref "SV3") (pin "42") (pinfunction "42_42") (pintype "passive"))
      (node (ref "SV5") (pin "42") (pinfunction "42_42") (pintype "passive"))
    )
    (net (code "36") (name "MCBMB00(0)") (class "Default")
      (node (ref "E14") (pin "2") (pinfunction "A1_2") (pintype "input"))
      (node (ref "H02") (pin "S2") (pinfunction "1_S2") (pintype "bidirectional"))
      (node (ref "SV2") (pin "38") (pinfunction "38_38") (pintype "passive"))
      (node (ref "SV3") (pin "38") (pinfunction "38_38") (pintype "passive"))
    )
    (net (code "37") (name "MCBMB01(0)") (class "Default")
      (node (ref "E14") (pin "4") (pinfunction "A2_4") (pintype "input"))
      (node (ref "H02") (pin "T2") (pinfunction "1_T2") (pintype "bidirectional"))
      (node (ref "SV2") (pin "35") (pinfunction "35_35") (pintype "passive"))
      (node (ref "SV3") (pin "35") (pinfunction "35_35") (pintype "passive"))
    )
    (net (code "38") (name "MCBMB02(0)") (class "Default")
      (node (ref "E14") (pin "6") (pinfunction "A3_6") (pintype "input"))
      (node (ref "H02") (pin "V2") (pinfunction "1_V2") (pintype "bidirectional"))
      (node (ref "SV2") (pin "36") (pinfunction "36_36") (pintype "passive"))
      (node (ref "SV3") (pin "36") (pinfunction "36_36") (pintype "passive"))
    )
    (net (code "39") (name "MCBMB03(0)") (class "Default")
      (node (ref "E14") (pin "8") (pinfunction "A4_8") (pintype "input"))
      (node (ref "H01") (pin "D2") (pinfunction "1_D2") (pintype "bidirectional"))
      (node (ref "SV1") (pin "46") (pinfunction "46_46") (pintype "passive"))
      (node (ref "SV3") (pin "46") (pinfunction "46_46") (pintype "passive"))
    )
    (net (code "40") (name "MCBMB04(0)") (class "Default")
      (node (ref "E14") (pin "11") (pinfunction "A1_11") (pintype "input"))
      (node (ref "H01") (pin "E2") (pinfunction "1_E2") (pintype "bidirectional"))
      (node (ref "SV1") (pin "44") (pinfunction "44_44") (pintype "passive"))
      (node (ref "SV3") (pin "44") (pinfunction "44_44") (pintype "passive"))
    )
    (net (code "41") (name "MCBMB05(0)") (class "Default")
      (node (ref "E14") (pin "13") (pinfunction "A2_13") (pintype "input"))
      (node (ref "H01") (pin "H2") (pinfunction "1_H2") (pintype "bidirectional"))
      (node (ref "SV1") (pin "43") (pinfunction "43_43") (pintype "passive"))
      (node (ref "SV3") (pin "43") (pinfunction "43_43") (pintype "passive"))
    )
    (net (code "42") (name "MCBMB06(0)") (class "Default")
      (node (ref "E14") (pin "15") (pinfunction "A3_15") (pintype "input"))
      (node (ref "H03") (pin "K2") (pinfunction "1_K2") (pintype "bidirectional"))
    )
    (net (code "43") (name "MCBMB07(0)") (class "Default")
      (node (ref "E14") (pin "17") (pinfunction "A4_17") (pintype "input"))
      (node (ref "H03") (pin "M2") (pinfunction "1_M2") (pintype "bidirectional"))
    )
    (net (code "44") (name "MCBMB08(0)") (class "Default")
      (node (ref "E15") (pin "2") (pinfunction "A1_2") (pintype "input"))
      (node (ref "H03") (pin "P2") (pinfunction "1_P2") (pintype "bidirectional"))
    )
    (net (code "45") (name "MCBMB09(0)") (class "Default")
      (node (ref "E15") (pin "4") (pinfunction "A2_4") (pintype "input"))
      (node (ref "H03") (pin "S2") (pinfunction "1_S2") (pintype "bidirectional"))
    )
    (net (code "46") (name "MCBMB10(0)") (class "Default")
      (node (ref "E15") (pin "6") (pinfunction "A3_6") (pintype "input"))
      (node (ref "H03") (pin "T2") (pinfunction "1_T2") (pintype "bidirectional"))
    )
    (net (code "47") (name "MCBMB11(0)") (class "Default")
      (node (ref "E15") (pin "8") (pinfunction "A4_8") (pintype "input"))
      (node (ref "H03") (pin "V2") (pinfunction "1_V2") (pintype "bidirectional"))
    )
    (net (code "48") (name "MEM00") (class "Default")
      (node (ref "E12") (pin "18") (pinfunction "Y1_18") (pintype "tri_state"))
      (node (ref "H04") (pin "E2") (pinfunction "1_E2") (pintype "bidirectional"))
    )
    (net (code "49") (name "MEM01") (class "Default")
      (node (ref "E12") (pin "16") (pinfunction "Y2_16") (pintype "tri_state"))
      (node (ref "H04") (pin "H2") (pinfunction "1_H2") (pintype "bidirectional"))
    )
    (net (code "50") (name "MEM02") (class "Default")
      (node (ref "E12") (pin "14") (pinfunction "Y3_14") (pintype "tri_state"))
      (node (ref "H04") (pin "K2") (pinfunction "1_K2") (pintype "bidirectional"))
    )
    (net (code "51") (name "MEM03") (class "Default")
      (node (ref "E12") (pin "12") (pinfunction "Y4_12") (pintype "tri_state"))
      (node (ref "H04") (pin "M2") (pinfunction "1_M2") (pintype "bidirectional"))
    )
    (net (code "52") (name "MEM04") (class "Default")
      (node (ref "E12") (pin "9") (pinfunction "Y1_9") (pintype "tri_state"))
      (node (ref "H04") (pin "P2") (pinfunction "1_P2") (pintype "bidirectional"))
    )
    (net (code "53") (name "MEM05") (class "Default")
      (node (ref "E12") (pin "7") (pinfunction "Y2_7") (pintype "tri_state"))
      (node (ref "H04") (pin "S2") (pinfunction "1_S2") (pintype "bidirectional"))
    )
    (net (code "54") (name "MEM06") (class "Default")
      (node (ref "E12") (pin "5") (pinfunction "Y3_5") (pintype "tri_state"))
      (node (ref "H04") (pin "T2") (pinfunction "1_T2") (pintype "bidirectional"))
    )
    (net (code "55") (name "MEM07") (class "Default")
      (node (ref "E12") (pin "3") (pinfunction "Y4_3") (pintype "tri_state"))
      (node (ref "H04") (pin "V2") (pinfunction "1_V2") (pintype "bidirectional"))
    )
    (net (code "56") (name "MEM08") (class "Default")
      (node (ref "E13") (pin "18") (pinfunction "Y1_18") (pintype "tri_state"))
      (node (ref "H05") (pin "D2") (pinfunction "1_D2") (pintype "bidirectional"))
      (node (ref "SV4") (pin "41") (pinfunction "41_41") (pintype "passive"))
      (node (ref "SV5") (pin "41") (pinfunction "41_41") (pintype "passive"))
    )
    (net (code "57") (name "MEM09") (class "Default")
      (node (ref "E13") (pin "16") (pinfunction "Y2_16") (pintype "tri_state"))
      (node (ref "H05") (pin "E2") (pinfunction "1_E2") (pintype "bidirectional"))
      (node (ref "SV4") (pin "39") (pinfunction "39_39") (pintype "passive"))
      (node (ref "SV5") (pin "39") (pinfunction "39_39") (pintype "passive"))
    )
    (net (code "58") (name "MEM10") (class "Default")
      (node (ref "E13") (pin "14") (pinfunction "Y3_14") (pintype "tri_state"))
      (node (ref "H05") (pin "H2") (pinfunction "1_H2") (pintype "bidirectional"))
      (node (ref "SV4") (pin "40") (pinfunction "40_40") (pintype "passive"))
      (node (ref "SV5") (pin "40") (pinfunction "40_40") (pintype "passive"))
    )
    (net (code "59") (name "MEM11") (class "Default")
      (node (ref "E13") (pin "12") (pinfunction "Y4_12") (pintype "tri_state"))
      (node (ref "H05") (pin "K2") (pinfunction "1_K2") (pintype "bidirectional"))
      (node (ref "SV4") (pin "37") (pinfunction "37_37") (pintype "passive"))
      (node (ref "SV5") (pin "37") (pinfunction "37_37") (pintype "passive"))
    )
    (net (code "60") (name "MEMDONE(0)") (class "Default")
      (node (ref "E4") (pin "13") (pinfunction "O_13") (pintype "open_collector"))
      (node (ref "H05") (pin "S2") (pinfunction "1_S2") (pintype "bidirectional"))
    )
    (net (code "61") (name "MEMDONE(1)") (class "Default")
      (node (ref "E2") (pin "5") (pinfunction "Q_5") (pintype "output"))
      (node (ref "E4") (pin "11") (pinfunction "I0_11") (pintype "input"))
      (node (ref "E4") (pin "12") (pinfunction "I1_12") (pintype "input"))
    )
    (net (code "62") (name "MEMSTART(0)") (class "Default")
      (node (ref "E3") (pin "1") (pinfunction "A_1") (pintype "input"))
      (node (ref "E3") (pin "9") (pinfunction "A_9") (pintype "input"))
      (node (ref "E5") (pin "6") (pinfunction "O_6") (pintype "output"))
    )
    (net (code "63") (name "MEMSTART(1)") (class "Default")
      (node (ref "E5") (pin "5") (pinfunction "I1_5") (pintype "input"))
      (node (ref "H05") (pin "M2") (pinfunction "1_M2") (pintype "bidirectional"))
      (node (ref "R1") (pin "1") (pinfunction "1_1") (pintype "passive"))
    )
    (net (code "64") (name "MEM_P") (class "Default")
      (node (ref "E13") (pin "9") (pinfunction "Y1_9") (pintype "tri_state"))
      (node (ref "H04") (pin "D2") (pinfunction "1_D2") (pintype "bidirectional"))
    )
    (net (code "65") (name "Net-(E1A-C)") (class "Default")
      (node (ref "C19") (pin "2") (pinfunction "2_2") (pintype "passive"))
      (node (ref "E1") (pin "14") (pinfunction "C_14") (pintype "input"))
    )
    (net (code "66") (name "Net-(E1A-R{slash}C)") (class "Default")
      (node (ref "C19") (pin "1") (pinfunction "1_1") (pintype "passive"))
      (node (ref "E1") (pin "15") (pinfunction "R/C_15") (pintype "input"))
      (node (ref "R6") (pin "2") (pinfunction "2_2") (pintype "passive"))
    )
    (net (code "67") (name "Net-(E1B-C)") (class "Default")
      (node (ref "C20") (pin "2") (pinfunction "2_2") (pintype "passive"))
      (node (ref "E1") (pin "6") (pinfunction "C_6") (pintype "input"))
    )
    (net (code "68") (name "Net-(E1B-R{slash}C)") (class "Default")
      (node (ref "C20") (pin "1") (pinfunction "1_1") (pintype "passive"))
      (node (ref "E1") (pin "7") (pinfunction "R/C_7") (pintype "input"))
      (node (ref "R7") (pin "2") (pinfunction "2_2") (pintype "passive"))
    )
    (net (code "69") (name "Net-(E2A-C)") (class "Default")
      (node (ref "C21") (pin "2") (pinfunction "2_2") (pintype "passive"))
      (node (ref "E2") (pin "14") (pinfunction "C_14") (pintype "input"))
    )
    (net (code "70") (name "Net-(E2A-R{slash}C)") (class "Default")
      (node (ref "C21") (pin "1") (pinfunction "1_1") (pintype "passive"))
      (node (ref "E2") (pin "15") (pinfunction "R/C_15") (pintype "input"))
      (node (ref "R8") (pin "2") (pinfunction "2_2") (pintype "passive"))
    )
    (net (code "71") (name "Net-(E2B-C)") (class "Default")
      (node (ref "C22") (pin "2") (pinfunction "2_2") (pintype "passive"))
      (node (ref "E2") (pin "6") (pinfunction "C_6") (pintype "input"))
    )
    (net (code "72") (name "Net-(E2B-R{slash}C)") (class "Default")
      (node (ref "C22") (pin "1") (pinfunction "1_1") (pintype "passive"))
      (node (ref "E2") (pin "7") (pinfunction "R/C_7") (pintype "input"))
      (node (ref "R9") (pin "2") (pinfunction "2_2") (pintype "passive"))
    )
    (net (code "73") (name "Net-(E3A-C)") (class "Default")
      (node (ref "C17") (pin "2") (pinfunction "2_2") (pintype "passive"))
      (node (ref "E3") (pin "14") (pinfunction "C_14") (pintype "input"))
    )
    (net (code "74") (name "Net-(E3A-R{slash}C)") (class "Default")
      (node (ref "C17") (pin "1") (pinfunction "1_1") (pintype "passive"))
      (node (ref "E3") (pin "15") (pinfunction "R/C_15") (pintype "input"))
      (node (ref "R4") (pin "2") (pinfunction "2_2") (pintype "passive"))
    )
    (net (code "75") (name "Net-(E3B-C)") (class "Default")
      (node (ref "C18") (pin "2") (pinfunction "2_2") (pintype "passive"))
      (node (ref "E3") (pin "6") (pinfunction "C_6") (pintype "input"))
    )
    (net (code "76") (name "Net-(E3B-R{slash}C)") (class "Default")
      (node (ref "C18") (pin "1") (pinfunction "1_1") (pintype "passive"))
      (node (ref "E3") (pin "7") (pinfunction "R/C_7") (pintype "input"))
      (node (ref "R5") (pin "2") (pinfunction "2_2") (pintype "passive"))
    )
    (net (code "77") (name "Net-(E16-I{slash}O5)") (class "Default")
      (node (ref "E16") (pin "17") (pinfunction "I/O5_17") (pintype "bidirectional"))
      (node (ref "E16A") (pin "17") (pinfunction "I/O5_17") (pintype "bidirectional"))
    )
    (net (code "78") (name "Net-(E16-I{slash}O6)") (class "Default")
      (node (ref "E16") (pin "18") (pinfunction "I/O6_18") (pintype "bidirectional"))
      (node (ref "E16A") (pin "18") (pinfunction "I/O6_18") (pintype "bidirectional"))
    )
    (net (code "79") (name "Net-(E16-I{slash}O7)") (class "Default")
      (node (ref "E16") (pin "19") (pinfunction "I/O7_19") (pintype "bidirectional"))
      (node (ref "E16A") (pin "19") (pinfunction "I/O7_19") (pintype "bidirectional"))
    )
    (net (code "80") (name "Net-(E18A-I0)") (class "Default")
      (node (ref "E18") (pin "1") (pinfunction "I0_1") (pintype "input"))
      (node (ref "FIELDS") (pin "2") (pinfunction "2_2") (pintype "passive"))
    )
    (net (code "81") (name "Net-(E18A-I1)") (class "Default")
      (node (ref "E18") (pin "2") (pinfunction "I1_2") (pintype "input"))
      (node (ref "FIELDS") (pin "4") (pinfunction "4_4") (pintype "passive"))
    )
    (net (code "82") (name "Net-(E18A-I2)") (class "Default")
      (node (ref "E18") (pin "3") (pinfunction "I2_3") (pintype "input"))
      (node (ref "FIELDS") (pin "6") (pinfunction "6_6") (pintype "passive"))
    )
    (net (code "83") (name "Net-(E18A-I3)") (class "Default")
      (node (ref "E18") (pin "4") (pinfunction "I3_4") (pintype "input"))
      (node (ref "FIELDS") (pin "8") (pinfunction "8_8") (pintype "passive"))
    )
    (net (code "84") (name "Net-(E18A-I4)") (class "Default")
      (node (ref "E18") (pin "5") (pinfunction "I4_5") (pintype "input"))
      (node (ref "FIELDS") (pin "10") (pinfunction "10_10") (pintype "passive"))
    )
    (net (code "85") (name "Net-(E18A-I5)") (class "Default")
      (node (ref "E18") (pin "6") (pinfunction "I5_6") (pintype "input"))
      (node (ref "FIELDS") (pin "12") (pinfunction "12_12") (pintype "passive"))
    )
    (net (code "86") (name "Net-(E18A-I6)") (class "Default")
      (node (ref "E18") (pin "11") (pinfunction "I6_11") (pintype "input"))
      (node (ref "FIELDS") (pin "16") (pinfunction "16_16") (pintype "passive"))
    )
    (net (code "87") (name "Net-(E18A-I7)") (class "Default")
      (node (ref "E18") (pin "12") (pinfunction "I7_12") (pintype "input"))
      (node (ref "FIELDS") (pin "14") (pinfunction "14_14") (pintype "passive"))
    )
    (net (code "88") (name "Net-(E19A-Y0)") (class "Default")
      (node (ref "E19") (pin "15") (pinfunction "Y0_15") (pintype "output"))
      (node (ref "FIELDS") (pin "1") (pinfunction "1_1") (pintype "passive"))
    )
    (net (code "89") (name "Net-(E19A-Y1)") (class "Default")
      (node (ref "E19") (pin "14") (pinfunction "Y1_14") (pintype "output"))
      (node (ref "FIELDS") (pin "3") (pinfunction "3_3") (pintype "passive"))
    )
    (net (code "90") (name "Net-(E19A-Y2)") (class "Default")
      (node (ref "E19") (pin "13") (pinfunction "Y2_13") (pintype "output"))
      (node (ref "FIELDS") (pin "5") (pinfunction "5_5") (pintype "passive"))
    )
    (net (code "91") (name "Net-(E19A-Y3)") (class "Default")
      (node (ref "E19") (pin "12") (pinfunction "Y3_12") (pintype "output"))
      (node (ref "FIELDS") (pin "7") (pinfunction "7_7") (pintype "passive"))
    )
    (net (code "92") (name "Net-(E19A-Y4)") (class "Default")
      (node (ref "E19") (pin "11") (pinfunction "Y4_11") (pintype "output"))
      (node (ref "FIELDS") (pin "9") (pinfunction "9_9") (pintype "passive"))
    )
    (net (code "93") (name "Net-(E19A-Y5)") (class "Default")
      (node (ref "E19") (pin "10") (pinfunction "Y5_10") (pintype "output"))
      (node (ref "FIELDS") (pin "11") (pinfunction "11_11") (pintype "passive"))
    )
    (net (code "94") (name "Net-(E19A-Y6)") (class "Default")
      (node (ref "E19") (pin "9") (pinfunction "Y6_9") (pintype "output"))
      (node (ref "FIELDS") (pin "13") (pinfunction "13_13") (pintype "passive"))
    )
    (net (code "95") (name "Net-(E19A-Y7)") (class "Default")
      (node (ref "E19") (pin "7") (pinfunction "Y7_7") (pintype "output"))
      (node (ref "FIELDS") (pin "15") (pinfunction "15_15") (pintype "passive"))
    )
    (net (code "96") (name "OE(0)") (class "Default")
      (node (ref "E12") (pin "1") (pinfunction "G_1") (pintype "input"))
      (node (ref "E12") (pin "19") (pinfunction "G_19") (pintype "input"))
      (node (ref "E13") (pin "1") (pinfunction "G_1") (pintype "input"))
      (node (ref "E13") (pin "19") (pinfunction "G_19") (pintype "input"))
      (node (ref "E16") (pin "22") (pinfunction "~{OE}_22") (pintype "input"))
      (node (ref "E16A") (pin "22") (pinfunction "~{OE}_22") (pintype "input"))
      (node (ref "E17") (pin "22") (pinfunction "~{OE}_22") (pintype "input"))
      (node (ref "E17A") (pin "22") (pinfunction "~{OE}_22") (pintype "input"))
      (node (ref "E3") (pin "4") (pinfunction "~{Q}_4") (pintype "output"))
      (node (ref "E5") (pin "10") (pinfunction "I1_10") (pintype "input"))
      (node (ref "SV2") (pin "22") (pinfunction "22_22") (pintype "passive"))
      (node (ref "SV4") (pin "22") (pinfunction "22_22") (pintype "passive"))
      (node (ref "SV5") (pin "22") (pinfunction "22_22") (pintype "passive"))
    )
    (net (code "97") (name "PARITY") (class "Default")
      (node (ref "E13") (pin "11") (pinfunction "A1_11") (pintype "input"))
      (node (ref "E13") (pin "13") (pinfunction "A2_13") (pintype "input"))
      (node (ref "E13") (pin "15") (pinfunction "A3_15") (pintype "input"))
      (node (ref "E13") (pin "17") (pinfunction "A4_17") (pintype "input"))
      (node (ref "E15") (pin "9") (pinfunction "Y1_9") (pintype "tri_state"))
      (node (ref "E16") (pin "16") (pinfunction "I/O4_16") (pintype "bidirectional"))
      (node (ref "E16A") (pin "16") (pinfunction "I/O4_16") (pintype "bidirectional"))
      (node (ref "SV2") (pin "3") (pinfunction "3_3") (pintype "passive"))
      (node (ref "SV3") (pin "3") (pinfunction "3_3") (pintype "passive"))
      (node (ref "SV4") (pin "3") (pinfunction "3_3") (pintype "passive"))
    )
    (net (code "98") (name "SDELAY") (class "Default")
      (node (ref "E2") (pin "1") (pinfunction "A_1") (pintype "input"))
      (node (ref "E3") (pin "5") (pinfunction "Q_5") (pintype "output"))
    )
    (net (code "99") (name "STROBE(0)") (class "Default")
      (node (ref "E4") (pin "10") (pinfunction "O_10") (pintype "open_collector"))
      (node (ref "H05") (pin "P2") (pinfunction "1_P2") (pintype "bidirectional"))
    )
    (net (code "100") (name "STROBE(1)") (class "Default")
      (node (ref "E2") (pin "13") (pinfunction "Q_13") (pintype "output"))
      (node (ref "E4") (pin "8") (pinfunction "I0_8") (pintype "input"))
      (node (ref "E4") (pin "9") (pinfunction "I1_9") (pintype "input"))
    )
    (net (code "101") (name "VCC") (class "Default")
      (node (ref "C10") (pin "1") (pinfunction "1_1") (pintype "passive"))
      (node (ref "C11") (pin "1") (pinfunction "1_1") (pintype "passive"))
      (node (ref "C12") (pin "1") (pinfunction "1_1") (pintype "passive"))
      (node (ref "C13") (pin "1") (pinfunction "1_1") (pintype "passive"))
      (node (ref "C14") (pin "1") (pinfunction "1_1") (pintype "passive"))
      (node (ref "C15") (pin "1") (pinfunction "1_1") (pintype "passive"))
      (node (ref "C16") (pin "1") (pinfunction "1_1") (pintype "passive"))
      (node (ref "C2") (pin "1") (pinfunction "1_1") (pintype "passive"))
      (node (ref "C3") (pin "1") (pinfunction "1_1") (pintype "passive"))
      (node (ref "C4") (pin "1") (pinfunction "1_1") (pintype "passive"))
      (node (ref "C5") (pin "1") (pinfunction "1_1") (pintype "passive"))
      (node (ref "C6") (pin "1") (pinfunction "1_1") (pintype "passive"))
      (node (ref "C9") (pin "1") (pinfunction "1_1") (pintype "passive"))
      (node (ref "E1") (pin "10") (pinfunction "B_10") (pintype "input"))
      (node (ref "E1") (pin "11") (pinfunction "CLR_11") (pintype "input"))
      (node (ref "E1") (pin "2") (pinfunction "B_2") (pintype "input"))
      (node (ref "E1") (pin "3") (pinfunction "CLR_3") (pintype "input"))
      (node (ref "E16") (pin "28") (pinfunction "VCC_28") (pintype "power_in"))
      (node (ref "E16A") (pin "28") (pinfunction "VCC_28") (pintype "power_in"))
      (node (ref "E17") (pin "28") (pinfunction "VCC_28") (pintype "power_in"))
      (node (ref "E17A") (pin "28") (pinfunction "VCC_28") (pintype "power_in"))
      (node (ref "E19") (pin "6") (pinfunction "G1_6") (pintype "input"))
      (node (ref "E2") (pin "10") (pinfunction "B_10") (pintype "input"))
      (node (ref "E2") (pin "11") (pinfunction "CLR_11") (pintype "input"))
      (node (ref "E2") (pin "2") (pinfunction "B_2") (pintype "input"))
      (node (ref "E2") (pin "3") (pinfunction "CLR_3") (pintype "input"))
      (node (ref "E3") (pin "10") (pinfunction "B_10") (pintype "input"))
      (node (ref "E3") (pin "11") (pinfunction "CLR_11") (pintype "input"))
      (node (ref "E3") (pin "2") (pinfunction "B_2") (pintype "input"))
      (node (ref "E3") (pin "3") (pinfunction "CLR_3") (pintype "input"))
      (node (ref "E4") (pin "2") (pinfunction "I0_2") (pintype "input"))
      (node (ref "E4") (pin "3") (pinfunction "I1_3") (pintype "input"))
      (node (ref "E4") (pin "5") (pinfunction "I0_5") (pintype "input"))
      (node (ref "E4") (pin "6") (pinfunction "I1_6") (pintype "input"))
      (node (ref "R4") (pin "1") (pinfunction "1_1") (pintype "passive"))
      (node (ref "R5") (pin "1") (pinfunction "1_1") (pintype "passive"))
      (node (ref "R6") (pin "1") (pinfunction "1_1") (pintype "passive"))
      (node (ref "R7") (pin "1") (pinfunction "1_1") (pintype "passive"))
      (node (ref "R8") (pin "1") (pinfunction "1_1") (pintype "passive"))
      (node (ref "R9") (pin "1") (pinfunction "1_1") (pintype "passive"))
      (node (ref "SV1") (pin "49") (pinfunction "49_49") (pintype "passive"))
      (node (ref "SV1") (pin "50") (pinfunction "50_50") (pintype "passive"))
      (node (ref "SV2") (pin "49") (pinfunction "49_49") (pintype "passive"))
      (node (ref "SV2") (pin "50") (pinfunction "50_50") (pintype "passive"))
      (node (ref "SV3") (pin "49") (pinfunction "49_49") (pintype "passive"))
      (node (ref "SV3") (pin "50") (pinfunction "50_50") (pintype "passive"))
      (node (ref "SV4") (pin "49") (pinfunction "49_49") (pintype "passive"))
      (node (ref "SV4") (pin "50") (pinfunction "50_50") (pintype "passive"))
      (node (ref "SV5") (pin "49") (pinfunction "49_49") (pintype "passive"))
      (node (ref "SV5") (pin "50") (pinfunction "50_50") (pintype "passive"))
      (node (ref "X1") (pin "1") (pinfunction "KL_1") (pintype "passive"))
    )
    (net (code "102") (name "WE(0)") (class "Default")
      (node (ref "E1") (pin "4") (pinfunction "~{Q}_4") (pintype "output"))
      (node (ref "E14") (pin "1") (pinfunction "G_1") (pintype "input"))
      (node (ref "E14") (pin "19") (pinfunction "G_19") (pintype "input"))
      (node (ref "E15") (pin "1") (pinfunction "G_1") (pintype "input"))
      (node (ref "E15") (pin "19") (pinfunction "G_19") (pintype "input"))
      (node (ref "E16") (pin "27") (pinfunction "~{WE}_27") (pintype "input"))
      (node (ref "E16A") (pin "27") (pinfunction "~{WE}_27") (pintype "input"))
      (node (ref "E17") (pin "27") (pinfunction "~{WE}_27") (pintype "input"))
      (node (ref "E17A") (pin "27") (pinfunction "~{WE}_27") (pintype "input"))
      (node (ref "E5") (pin "9") (pinfunction "I0_9") (pintype "input"))
      (node (ref "SV2") (pin "32") (pinfunction "32_32") (pintype "passive"))
      (node (ref "SV3") (pin "32") (pinfunction "32_32") (pintype "passive"))
      (node (ref "SV5") (pin "32") (pinfunction "32_32") (pintype "passive"))
    )
    (net (code "103") (name "unconnected-(E1A-Q-Pad13)") (class "Default")
      (node (ref "E1") (pin "13") (pinfunction "Q_13") (pintype "output"))
    )
    (net (code "104") (name "unconnected-(E1B-~{Q}-Pad12)") (class "Default")
      (node (ref "E1") (pin "12") (pinfunction "~{Q}_12") (pintype "output"))
    )
    (net (code "105") (name "unconnected-(E2A-~{Q}-Pad4)") (class "Default")
      (node (ref "E2") (pin "4") (pinfunction "~{Q}_4") (pintype "output"))
    )
    (net (code "106") (name "unconnected-(E2B-~{Q}-Pad12)") (class "Default")
      (node (ref "E2") (pin "12") (pinfunction "~{Q}_12") (pintype "output"))
    )
    (net (code "107") (name "unconnected-(E3A-Q-Pad13)") (class "Default")
      (node (ref "E3") (pin "13") (pinfunction "Q_13") (pintype "output"))
    )
    (net (code "108") (name "unconnected-(E3B-~{Q}-Pad12)") (class "Default")
      (node (ref "E3") (pin "12") (pinfunction "~{Q}_12") (pintype "output"))
    )
    (net (code "109") (name "unconnected-(E4A-O-Pad1)") (class "Default")
      (node (ref "E4") (pin "1") (pinfunction "O_1") (pintype "open_collector"))
    )
    (net (code "110") (name "unconnected-(E4B-O-Pad4)") (class "Default")
      (node (ref "E4") (pin "4") (pinfunction "O_4") (pintype "open_collector"))
    )
    (net (code "111") (name "unconnected-(E13B-Y2-Pad7)") (class "Default")
      (node (ref "E13") (pin "7") (pinfunction "Y2_7") (pintype "tri_state"))
    )
    (net (code "112") (name "unconnected-(E13B-Y3-Pad5)") (class "Default")
      (node (ref "E13") (pin "5") (pinfunction "Y3_5") (pintype "tri_state"))
    )
    (net (code "113") (name "unconnected-(E13B-Y4-Pad3)") (class "Default")
      (node (ref "E13") (pin "3") (pinfunction "Y4_3") (pintype "tri_state"))
    )
    (net (code "114") (name "unconnected-(E15B-Y2-Pad7)") (class "Default")
      (node (ref "E15") (pin "7") (pinfunction "Y2_7") (pintype "tri_state"))
    )
    (net (code "115") (name "unconnected-(E15B-Y3-Pad5)") (class "Default")
      (node (ref "E15") (pin "5") (pinfunction "Y3_5") (pintype "tri_state"))
    )
    (net (code "116") (name "unconnected-(E15B-Y4-Pad3)") (class "Default")
      (node (ref "E15") (pin "3") (pinfunction "Y4_3") (pintype "tri_state"))
    )
    (net (code "117") (name "unconnected-(SV1-Pad3)") (class "Default")
      (node (ref "SV1") (pin "3") (pinfunction "3_3") (pintype "passive"))
    )
    (net (code "118") (name "unconnected-(SV1-Pad4)") (class "Default")
      (node (ref "SV1") (pin "4") (pinfunction "4_4") (pintype "passive"))
    )
    (net (code "119") (name "unconnected-(SV1-Pad5)") (class "Default")
      (node (ref "SV1") (pin "5") (pinfunction "5_5") (pintype "passive"))
    )
    (net (code "120") (name "unconnected-(SV1-Pad6)") (class "Default")
      (node (ref "SV1") (pin "6") (pinfunction "6_6") (pintype "passive"))
    )
    (net (code "121") (name "unconnected-(SV1-Pad7)") (class "Default")
      (node (ref "SV1") (pin "7") (pinfunction "7_7") (pintype "passive"))
    )
    (net (code "122") (name "unconnected-(SV1-Pad8)") (class "Default")
      (node (ref "SV1") (pin "8") (pinfunction "8_8") (pintype "passive"))
    )
    (net (code "123") (name "unconnected-(SV1-Pad9)") (class "Default")
      (node (ref "SV1") (pin "9") (pinfunction "9_9") (pintype "passive"))
    )
    (net (code "124") (name "unconnected-(SV1-Pad10)") (class "Default")
      (node (ref "SV1") (pin "10") (pinfunction "10_10") (pintype "passive"))
    )
    (net (code "125") (name "unconnected-(SV1-Pad11)") (class "Default")
      (node (ref "SV1") (pin "11") (pinfunction "11_11") (pintype "passive"))
    )
    (net (code "126") (name "unconnected-(SV1-Pad12)") (class "Default")
      (node (ref "SV1") (pin "12") (pinfunction "12_12") (pintype "passive"))
    )
    (net (code "127") (name "unconnected-(SV1-Pad13)") (class "Default")
      (node (ref "SV1") (pin "13") (pinfunction "13_13") (pintype "passive"))
    )
    (net (code "128") (name "unconnected-(SV1-Pad14)") (class "Default")
      (node (ref "SV1") (pin "14") (pinfunction "14_14") (pintype "passive"))
    )
    (net (code "129") (name "unconnected-(SV1-Pad15)") (class "Default")
      (node (ref "SV1") (pin "15") (pinfunction "15_15") (pintype "passive"))
    )
    (net (code "130") (name "unconnected-(SV1-Pad16)") (class "Default")
      (node (ref "SV1") (pin "16") (pinfunction "16_16") (pintype "passive"))
    )
    (net (code "131") (name "unconnected-(SV1-Pad17)") (class "Default")
      (node (ref "SV1") (pin "17") (pinfunction "17_17") (pintype "passive"))
    )
    (net (code "132") (name "unconnected-(SV1-Pad18)") (class "Default")
      (node (ref "SV1") (pin "18") (pinfunction "18_18") (pintype "passive"))
    )
    (net (code "133") (name "unconnected-(SV1-Pad19)") (class "Default")
      (node (ref "SV1") (pin "19") (pinfunction "19_19") (pintype "passive"))
    )
    (net (code "134") (name "unconnected-(SV1-Pad21)") (class "Default")
      (node (ref "SV1") (pin "21") (pinfunction "21_21") (pintype "passive"))
    )
    (net (code "135") (name "unconnected-(SV1-Pad22)") (class "Default")
      (node (ref "SV1") (pin "22") (pinfunction "22_22") (pintype "passive"))
    )
    (net (code "136") (name "unconnected-(SV1-Pad23)") (class "Default")
      (node (ref "SV1") (pin "23") (pinfunction "23_23") (pintype "passive"))
    )
    (net (code "137") (name "unconnected-(SV1-Pad25)") (class "Default")
      (node (ref "SV1") (pin "25") (pinfunction "25_25") (pintype "passive"))
    )
    (net (code "138") (name "unconnected-(SV1-Pad32)") (class "Default")
      (node (ref "SV1") (pin "32") (pinfunction "32_32") (pintype "passive"))
    )
    (net (code "139") (name "unconnected-(SV1-Pad35)") (class "Default")
      (node (ref "SV1") (pin "35") (pinfunction "35_35") (pintype "passive"))
    )
    (net (code "140") (name "unconnected-(SV1-Pad36)") (class "Default")
      (node (ref "SV1") (pin "36") (pinfunction "36_36") (pintype "passive"))
    )
    (net (code "141") (name "unconnected-(SV1-Pad37)") (class "Default")
      (node (ref "SV1") (pin "37") (pinfunction "37_37") (pintype "passive"))
    )
    (net (code "142") (name "unconnected-(SV1-Pad38)") (class "Default")
      (node (ref "SV1") (pin "38") (pinfunction "38_38") (pintype "passive"))
    )
    (net (code "143") (name "unconnected-(SV1-Pad39)") (class "Default")
      (node (ref "SV1") (pin "39") (pinfunction "39_39") (pintype "passive"))
    )
    (net (code "144") (name "unconnected-(SV1-Pad40)") (class "Default")
      (node (ref "SV1") (pin "40") (pinfunction "40_40") (pintype "passive"))
    )
    (net (code "145") (name "unconnected-(SV1-Pad41)") (class "Default")
      (node (ref "SV1") (pin "41") (pinfunction "41_41") (pintype "passive"))
    )
    (net (code "146") (name "unconnected-(SV1-Pad42)") (class "Default")
      (node (ref "SV1") (pin "42") (pinfunction "42_42") (pintype "passive"))
    )
    (net (code "147") (name "unconnected-(SV1-Pad45)") (class "Default")
      (node (ref "SV1") (pin "45") (pinfunction "45_45") (pintype "passive"))
    )
    (net (code "148") (name "unconnected-(SV1-Pad47)") (class "Default")
      (node (ref "SV1") (pin "47") (pinfunction "47_47") (pintype "passive"))
    )
    (net (code "149") (name "unconnected-(SV1-Pad48)") (class "Default")
      (node (ref "SV1") (pin "48") (pinfunction "48_48") (pintype "passive"))
    )
    (net (code "150") (name "unconnected-(SV2-Pad34)") (class "Default")
      (node (ref "SV2") (pin "34") (pinfunction "34_34") (pintype "passive"))
    )
    (net (code "151") (name "unconnected-(SV2-Pad37)") (class "Default")
      (node (ref "SV2") (pin "37") (pinfunction "37_37") (pintype "passive"))
    )
    (net (code "152") (name "unconnected-(SV2-Pad39)") (class "Default")
      (node (ref "SV2") (pin "39") (pinfunction "39_39") (pintype "passive"))
    )
    (net (code "153") (name "unconnected-(SV2-Pad40)") (class "Default")
      (node (ref "SV2") (pin "40") (pinfunction "40_40") (pintype "passive"))
    )
    (net (code "154") (name "unconnected-(SV2-Pad41)") (class "Default")
      (node (ref "SV2") (pin "41") (pinfunction "41_41") (pintype "passive"))
    )
    (net (code "155") (name "unconnected-(SV2-Pad42)") (class "Default")
      (node (ref "SV2") (pin "42") (pinfunction "42_42") (pintype "passive"))
    )
    (net (code "156") (name "unconnected-(SV2-Pad43)") (class "Default")
      (node (ref "SV2") (pin "43") (pinfunction "43_43") (pintype "passive"))
    )
    (net (code "157") (name "unconnected-(SV2-Pad44)") (class "Default")
      (node (ref "SV2") (pin "44") (pinfunction "44_44") (pintype "passive"))
    )
    (net (code "158") (name "unconnected-(SV2-Pad45)") (class "Default")
      (node (ref "SV2") (pin "45") (pinfunction "45_45") (pintype "passive"))
    )
    (net (code "159") (name "unconnected-(SV2-Pad46)") (class "Default")
      (node (ref "SV2") (pin "46") (pinfunction "46_46") (pintype "passive"))
    )
    (net (code "160") (name "unconnected-(SV2-Pad47)") (class "Default")
      (node (ref "SV2") (pin "47") (pinfunction "47_47") (pintype "passive"))
    )
    (net (code "161") (name "unconnected-(SV2-Pad48)") (class "Default")
      (node (ref "SV2") (pin "48") (pinfunction "48_48") (pintype "passive"))
    )
    (net (code "162") (name "unconnected-(SV3-Pad15)") (class "Default")
      (node (ref "SV3") (pin "15") (pinfunction "15_15") (pintype "passive"))
    )
    (net (code "163") (name "unconnected-(SV3-Pad17)") (class "Default")
      (node (ref "SV3") (pin "17") (pinfunction "17_17") (pintype "passive"))
    )
    (net (code "164") (name "unconnected-(SV3-Pad18)") (class "Default")
      (node (ref "SV3") (pin "18") (pinfunction "18_18") (pintype "passive"))
    )
    (net (code "165") (name "unconnected-(SV3-Pad19)") (class "Default")
      (node (ref "SV3") (pin "19") (pinfunction "19_19") (pintype "passive"))
    )
    (net (code "166") (name "unconnected-(SV3-Pad20)") (class "Default")
      (node (ref "SV3") (pin "20") (pinfunction "20_20") (pintype "passive"))
    )
    (net (code "167") (name "unconnected-(SV3-Pad21)") (class "Default")
      (node (ref "SV3") (pin "21") (pinfunction "21_21") (pintype "passive"))
    )
    (net (code "168") (name "unconnected-(SV3-Pad22)") (class "Default")
      (node (ref "SV3") (pin "22") (pinfunction "22_22") (pintype "passive"))
    )
    (net (code "169") (name "unconnected-(SV3-Pad23)") (class "Default")
      (node (ref "SV3") (pin "23") (pinfunction "23_23") (pintype "passive"))
    )
    (net (code "170") (name "unconnected-(SV3-Pad24)") (class "Default")
      (node (ref "SV3") (pin "24") (pinfunction "24_24") (pintype "passive"))
    )
    (net (code "171") (name "unconnected-(SV3-Pad25)") (class "Default")
      (node (ref "SV3") (pin "25") (pinfunction "25_25") (pintype "passive"))
    )
    (net (code "172") (name "unconnected-(SV3-Pad26)") (class "Default")
      (node (ref "SV3") (pin "26") (pinfunction "26_26") (pintype "passive"))
    )
    (net (code "173") (name "unconnected-(SV3-Pad27)") (class "Default")
      (node (ref "SV3") (pin "27") (pinfunction "27_27") (pintype "passive"))
    )
    (net (code "174") (name "unconnected-(SV3-Pad28)") (class "Default")
      (node (ref "SV3") (pin "28") (pinfunction "28_28") (pintype "passive"))
    )
    (net (code "175") (name "unconnected-(SV3-Pad29)") (class "Default")
      (node (ref "SV3") (pin "29") (pinfunction "29_29") (pintype "passive"))
    )
    (net (code "176") (name "unconnected-(SV3-Pad34)") (class "Default")
      (node (ref "SV3") (pin "34") (pinfunction "34_34") (pintype "passive"))
    )
    (net (code "177") (name "unconnected-(SV3-Pad37)") (class "Default")
      (node (ref "SV3") (pin "37") (pinfunction "37_37") (pintype "passive"))
    )
    (net (code "178") (name "unconnected-(SV3-Pad39)") (class "Default")
      (node (ref "SV3") (pin "39") (pinfunction "39_39") (pintype "passive"))
    )
    (net (code "179") (name "unconnected-(SV3-Pad40)") (class "Default")
      (node (ref "SV3") (pin "40") (pinfunction "40_40") (pintype "passive"))
    )
    (net (code "180") (name "unconnected-(SV3-Pad41)") (class "Default")
      (node (ref "SV3") (pin "41") (pinfunction "41_41") (pintype "passive"))
    )
    (net (code "181") (name "unconnected-(SV3-Pad45)") (class "Default")
      (node (ref "SV3") (pin "45") (pinfunction "45_45") (pintype "passive"))
    )
    (net (code "182") (name "unconnected-(SV3-Pad47)") (class "Default")
      (node (ref "SV3") (pin "47") (pinfunction "47_47") (pintype "passive"))
    )
    (net (code "183") (name "unconnected-(SV3-Pad48)") (class "Default")
      (node (ref "SV3") (pin "48") (pinfunction "48_48") (pintype "passive"))
    )
    (net (code "184") (name "unconnected-(SV4-Pad15)") (class "Default")
      (node (ref "SV4") (pin "15") (pinfunction "15_15") (pintype "passive"))
    )
    (net (code "185") (name "unconnected-(SV4-Pad17)") (class "Default")
      (node (ref "SV4") (pin "17") (pinfunction "17_17") (pintype "passive"))
    )
    (net (code "186") (name "unconnected-(SV4-Pad18)") (class "Default")
      (node (ref "SV4") (pin "18") (pinfunction "18_18") (pintype "passive"))
    )
    (net (code "187") (name "unconnected-(SV4-Pad19)") (class "Default")
      (node (ref "SV4") (pin "19") (pinfunction "19_19") (pintype "passive"))
    )
    (net (code "188") (name "unconnected-(SV4-Pad20)") (class "Default")
      (node (ref "SV4") (pin "20") (pinfunction "20_20") (pintype "passive"))
    )
    (net (code "189") (name "unconnected-(SV4-Pad21)") (class "Default")
      (node (ref "SV4") (pin "21") (pinfunction "21_21") (pintype "passive"))
    )
    (net (code "190") (name "unconnected-(SV4-Pad23)") (class "Default")
      (node (ref "SV4") (pin "23") (pinfunction "23_23") (pintype "passive"))
    )
    (net (code "191") (name "unconnected-(SV4-Pad24)") (class "Default")
      (node (ref "SV4") (pin "24") (pinfunction "24_24") (pintype "passive"))
    )
    (net (code "192") (name "unconnected-(SV4-Pad25)") (class "Default")
      (node (ref "SV4") (pin "25") (pinfunction "25_25") (pintype "passive"))
    )
    (net (code "193") (name "unconnected-(SV4-Pad26)") (class "Default")
      (node (ref "SV4") (pin "26") (pinfunction "26_26") (pintype "passive"))
    )
    (net (code "194") (name "unconnected-(SV4-Pad27)") (class "Default")
      (node (ref "SV4") (pin "27") (pinfunction "27_27") (pintype "passive"))
    )
    (net (code "195") (name "unconnected-(SV4-Pad28)") (class "Default")
      (node (ref "SV4") (pin "28") (pinfunction "28_28") (pintype "passive"))
    )
    (net (code "196") (name "unconnected-(SV4-Pad29)") (class "Default")
      (node (ref "SV4") (pin "29") (pinfunction "29_29") (pintype "passive"))
    )
    (net (code "197") (name "unconnected-(SV4-Pad30)") (class "Default")
      (node (ref "SV4") (pin "30") (pinfunction "30_30") (pintype "passive"))
    )
    (net (code "198") (name "unconnected-(SV4-Pad31)") (class "Default")
      (node (ref "SV4") (pin "31") (pinfunction "31_31") (pintype "passive"))
    )
    (net (code "199") (name "unconnected-(SV4-Pad32)") (class "Default")
      (node (ref "SV4") (pin "32") (pinfunction "32_32") (pintype "passive"))
    )
    (net (code "200") (name "unconnected-(SV4-Pad33)") (class "Default")
      (node (ref "SV4") (pin "33") (pinfunction "33_33") (pintype "passive"))
    )
    (net (code "201") (name "unconnected-(SV4-Pad34)") (class "Default")
      (node (ref "SV4") (pin "34") (pinfunction "34_34") (pintype "passive"))
    )
    (net (code "202") (name "unconnected-(SV4-Pad35)") (class "Default")
      (node (ref "SV4") (pin "35") (pinfunction "35_35") (pintype "passive"))
    )
    (net (code "203") (name "unconnected-(SV4-Pad36)") (class "Default")
      (node (ref "SV4") (pin "36") (pinfunction "36_36") (pintype "passive"))
    )
    (net (code "204") (name "unconnected-(SV4-Pad38)") (class "Default")
      (node (ref "SV4") (pin "38") (pinfunction "38_38") (pintype "passive"))
    )
    (net (code "205") (name "unconnected-(SV4-Pad42)") (class "Default")
      (node (ref "SV4") (pin "42") (pinfunction "42_42") (pintype "passive"))
    )
    (net (code "206") (name "unconnected-(SV4-Pad43)") (class "Default")
      (node (ref "SV4") (pin "43") (pinfunction "43_43") (pintype "passive"))
    )
    (net (code "207") (name "unconnected-(SV4-Pad44)") (class "Default")
      (node (ref "SV4") (pin "44") (pinfunction "44_44") (pintype "passive"))
    )
    (net (code "208") (name "unconnected-(SV4-Pad45)") (class "Default")
      (node (ref "SV4") (pin "45") (pinfunction "45_45") (pintype "passive"))
    )
    (net (code "209") (name "unconnected-(SV4-Pad46)") (class "Default")
      (node (ref "SV4") (pin "46") (pinfunction "46_46") (pintype "passive"))
    )
    (net (code "210") (name "unconnected-(SV4-Pad47)") (class "Default")
      (node (ref "SV4") (pin "47") (pinfunction "47_47") (pintype "passive"))
    )
    (net (code "211") (name "unconnected-(SV4-Pad48)") (class "Default")
      (node (ref "SV4") (pin "48") (pinfunction "48_48") (pintype "passive"))
    )
    (net (code "212") (name "unconnected-(SV5-Pad3)") (class "Default")
      (node (ref "SV5") (pin "3") (pinfunction "3_3") (pintype "passive"))
    )
    (net (code "213") (name "unconnected-(SV5-Pad4)") (class "Default")
      (node (ref "SV5") (pin "4") (pinfunction "4_4") (pintype "passive"))
    )
    (net (code "214") (name "unconnected-(SV5-Pad5)") (class "Default")
      (node (ref "SV5") (pin "5") (pinfunction "5_5") (pintype "passive"))
    )
    (net (code "215") (name "unconnected-(SV5-Pad6)") (class "Default")
      (node (ref "SV5") (pin "6") (pinfunction "6_6") (pintype "passive"))
    )
    (net (code "216") (name "unconnected-(SV5-Pad7)") (class "Default")
      (node (ref "SV5") (pin "7") (pinfunction "7_7") (pintype "passive"))
    )
    (net (code "217") (name "unconnected-(SV5-Pad8)") (class "Default")
      (node (ref "SV5") (pin "8") (pinfunction "8_8") (pintype "passive"))
    )
    (net (code "218") (name "unconnected-(SV5-Pad9)") (class "Default")
      (node (ref "SV5") (pin "9") (pinfunction "9_9") (pintype "passive"))
    )
    (net (code "219") (name "unconnected-(SV5-Pad10)") (class "Default")
      (node (ref "SV5") (pin "10") (pinfunction "10_10") (pintype "passive"))
    )
    (net (code "220") (name "unconnected-(SV5-Pad11)") (class "Default")
      (node (ref "SV5") (pin "11") (pinfunction "11_11") (pintype "passive"))
    )
    (net (code "221") (name "unconnected-(SV5-Pad12)") (class "Default")
      (node (ref "SV5") (pin "12") (pinfunction "12_12") (pintype "passive"))
    )
    (net (code "222") (name "unconnected-(SV5-Pad13)") (class "Default")
      (node (ref "SV5") (pin "13") (pinfunction "13_13") (pintype "passive"))
    )
    (net (code "223") (name "unconnected-(SV5-Pad14)") (class "Default")
      (node (ref "SV5") (pin "14") (pinfunction "14_14") (pintype "passive"))
    )
    (net (code "224") (name "unconnected-(SV5-Pad15)") (class "Default")
      (node (ref "SV5") (pin "15") (pinfunction "15_15") (pintype "passive"))
    )
    (net (code "225") (name "unconnected-(SV5-Pad16)") (class "Default")
      (node (ref "SV5") (pin "16") (pinfunction "16_16") (pintype "passive"))
    )
    (net (code "226") (name "unconnected-(SV5-Pad17)") (class "Default")
      (node (ref "SV5") (pin "17") (pinfunction "17_17") (pintype "passive"))
    )
    (net (code "227") (name "unconnected-(SV5-Pad19)") (class "Default")
      (node (ref "SV5") (pin "19") (pinfunction "19_19") (pintype "passive"))
    )
    (net (code "228") (name "unconnected-(SV5-Pad20)") (class "Default")
      (node (ref "SV5") (pin "20") (pinfunction "20_20") (pintype "passive"))
    )
    (net (code "229") (name "unconnected-(SV5-Pad21)") (class "Default")
      (node (ref "SV5") (pin "21") (pinfunction "21_21") (pintype "passive"))
    )
    (net (code "230") (name "unconnected-(SV5-Pad23)") (class "Default")
      (node (ref "SV5") (pin "23") (pinfunction "23_23") (pintype "passive"))
    )
    (net (code "231") (name "unconnected-(SV5-Pad24)") (class "Default")
      (node (ref "SV5") (pin "24") (pinfunction "24_24") (pintype "passive"))
    )
    (net (code "232") (name "unconnected-(SV5-Pad25)") (class "Default")
      (node (ref "SV5") (pin "25") (pinfunction "25_25") (pintype "passive"))
    )
    (net (code "233") (name "unconnected-(SV5-Pad26)") (class "Default")
      (node (ref "SV5") (pin "26") (pinfunction "26_26") (pintype "passive"))
    )
    (net (code "234") (name "unconnected-(SV5-Pad27)") (class "Default")
      (node (ref "SV5") (pin "27") (pinfunction "27_27") (pintype "passive"))
    )
    (net (code "235") (name "unconnected-(SV5-Pad28)") (class "Default")
      (node (ref "SV5") (pin "28") (pinfunction "28_28") (pintype "passive"))
    )
    (net (code "236") (name "unconnected-(SV5-Pad29)") (class "Default")
      (node (ref "SV5") (pin "29") (pinfunction "29_29") (pintype "passive"))
    )
    (net (code "237") (name "unconnected-(SV5-Pad30)") (class "Default")
      (node (ref "SV5") (pin "30") (pinfunction "30_30") (pintype "passive"))
    )
    (net (code "238") (name "unconnected-(SV5-Pad31)") (class "Default")
      (node (ref "SV5") (pin "31") (pinfunction "31_31") (pintype "passive"))
    )
    (net (code "239") (name "unconnected-(SV5-Pad33)") (class "Default")
      (node (ref "SV5") (pin "33") (pinfunction "33_33") (pintype "passive"))
    )
    (net (code "240") (name "unconnected-(SV5-Pad35)") (class "Default")
      (node (ref "SV5") (pin "35") (pinfunction "35_35") (pintype "passive"))
    )
    (net (code "241") (name "unconnected-(SV5-Pad36)") (class "Default")
      (node (ref "SV5") (pin "36") (pinfunction "36_36") (pintype "passive"))
    )
    (net (code "242") (name "unconnected-(SV5-Pad38)") (class "Default")
      (node (ref "SV5") (pin "38") (pinfunction "38_38") (pintype "passive"))
    )
    (net (code "243") (name "unconnected-(SV5-Pad43)") (class "Default")
      (node (ref "SV5") (pin "43") (pinfunction "43_43") (pintype "passive"))
    )
    (net (code "244") (name "unconnected-(SV5-Pad44)") (class "Default")
      (node (ref "SV5") (pin "44") (pinfunction "44_44") (pintype "passive"))
    )
    (net (code "245") (name "unconnected-(SV5-Pad45)") (class "Default")
      (node (ref "SV5") (pin "45") (pinfunction "45_45") (pintype "passive"))
    )
    (net (code "246") (name "unconnected-(SV5-Pad46)") (class "Default")
      (node (ref "SV5") (pin "46") (pinfunction "46_46") (pintype "passive"))
    )
    (net (code "247") (name "unconnected-(SV5-Pad47)") (class "Default")
      (node (ref "SV5") (pin "47") (pinfunction "47_47") (pintype "passive"))
    )
    (net (code "248") (name "unconnected-(SV5-Pad48)") (class "Default")
      (node (ref "SV5") (pin "48") (pinfunction "48_48") (pintype "passive"))
    )
  )
)
